# SCH-HC15C_REV1_PG2.net
KiCad netlist of a schematic drawn in Altium Designer
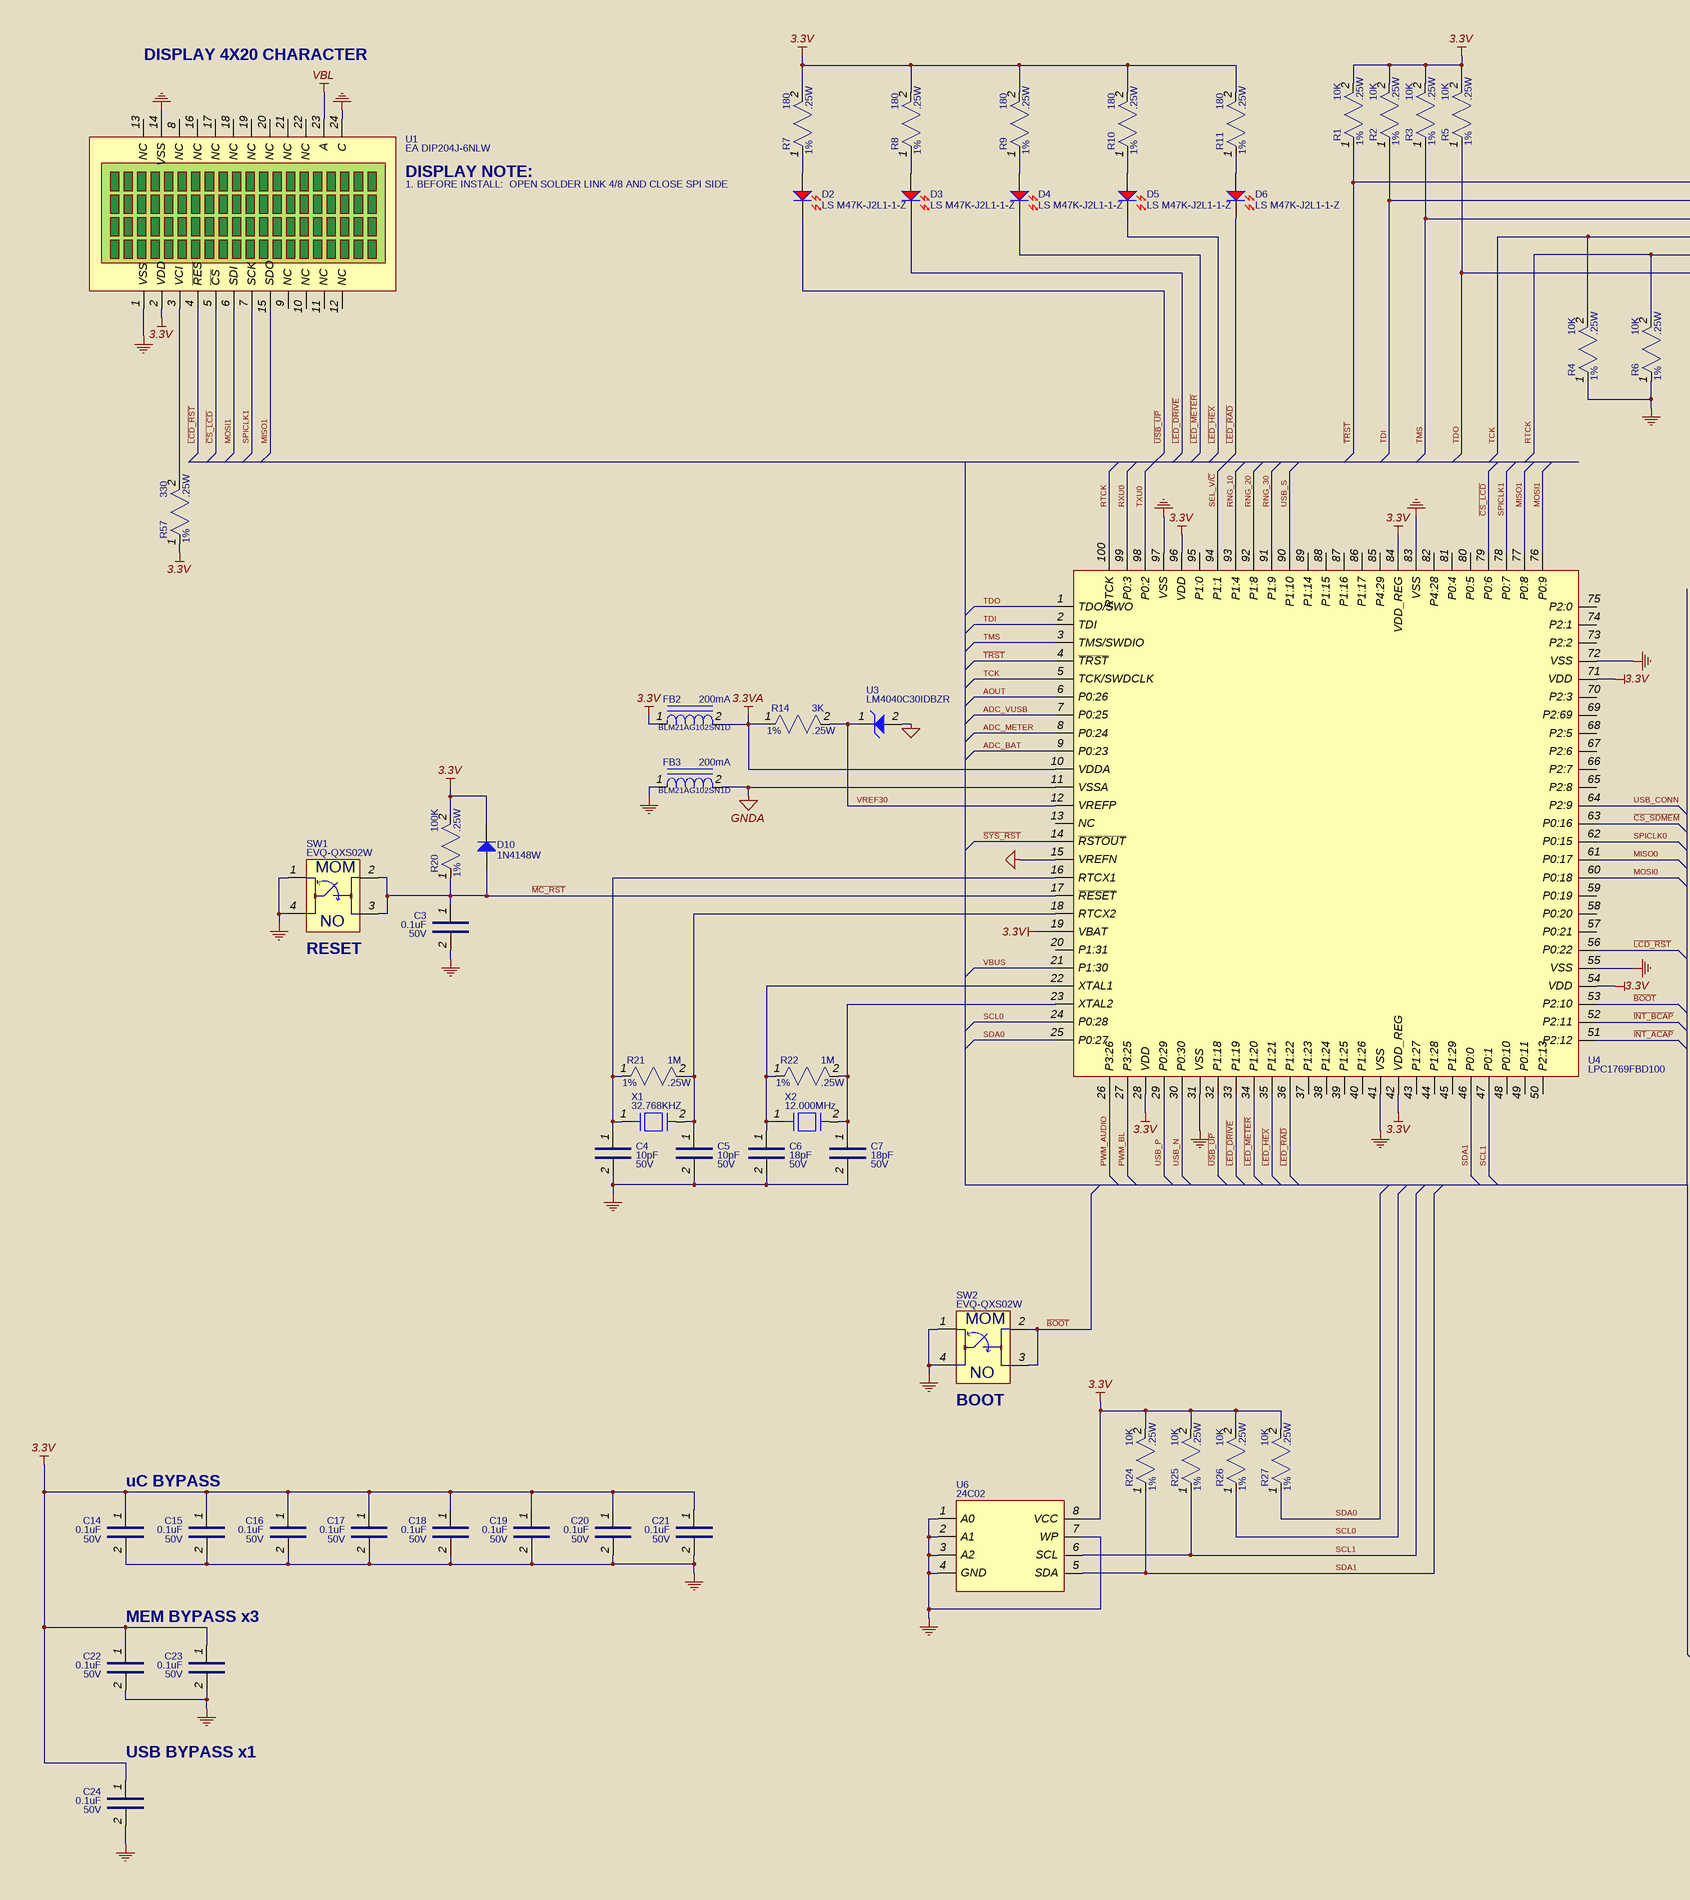
[diagram p0: SCH-HC15C_REV1_PG2.SchDoc, left]
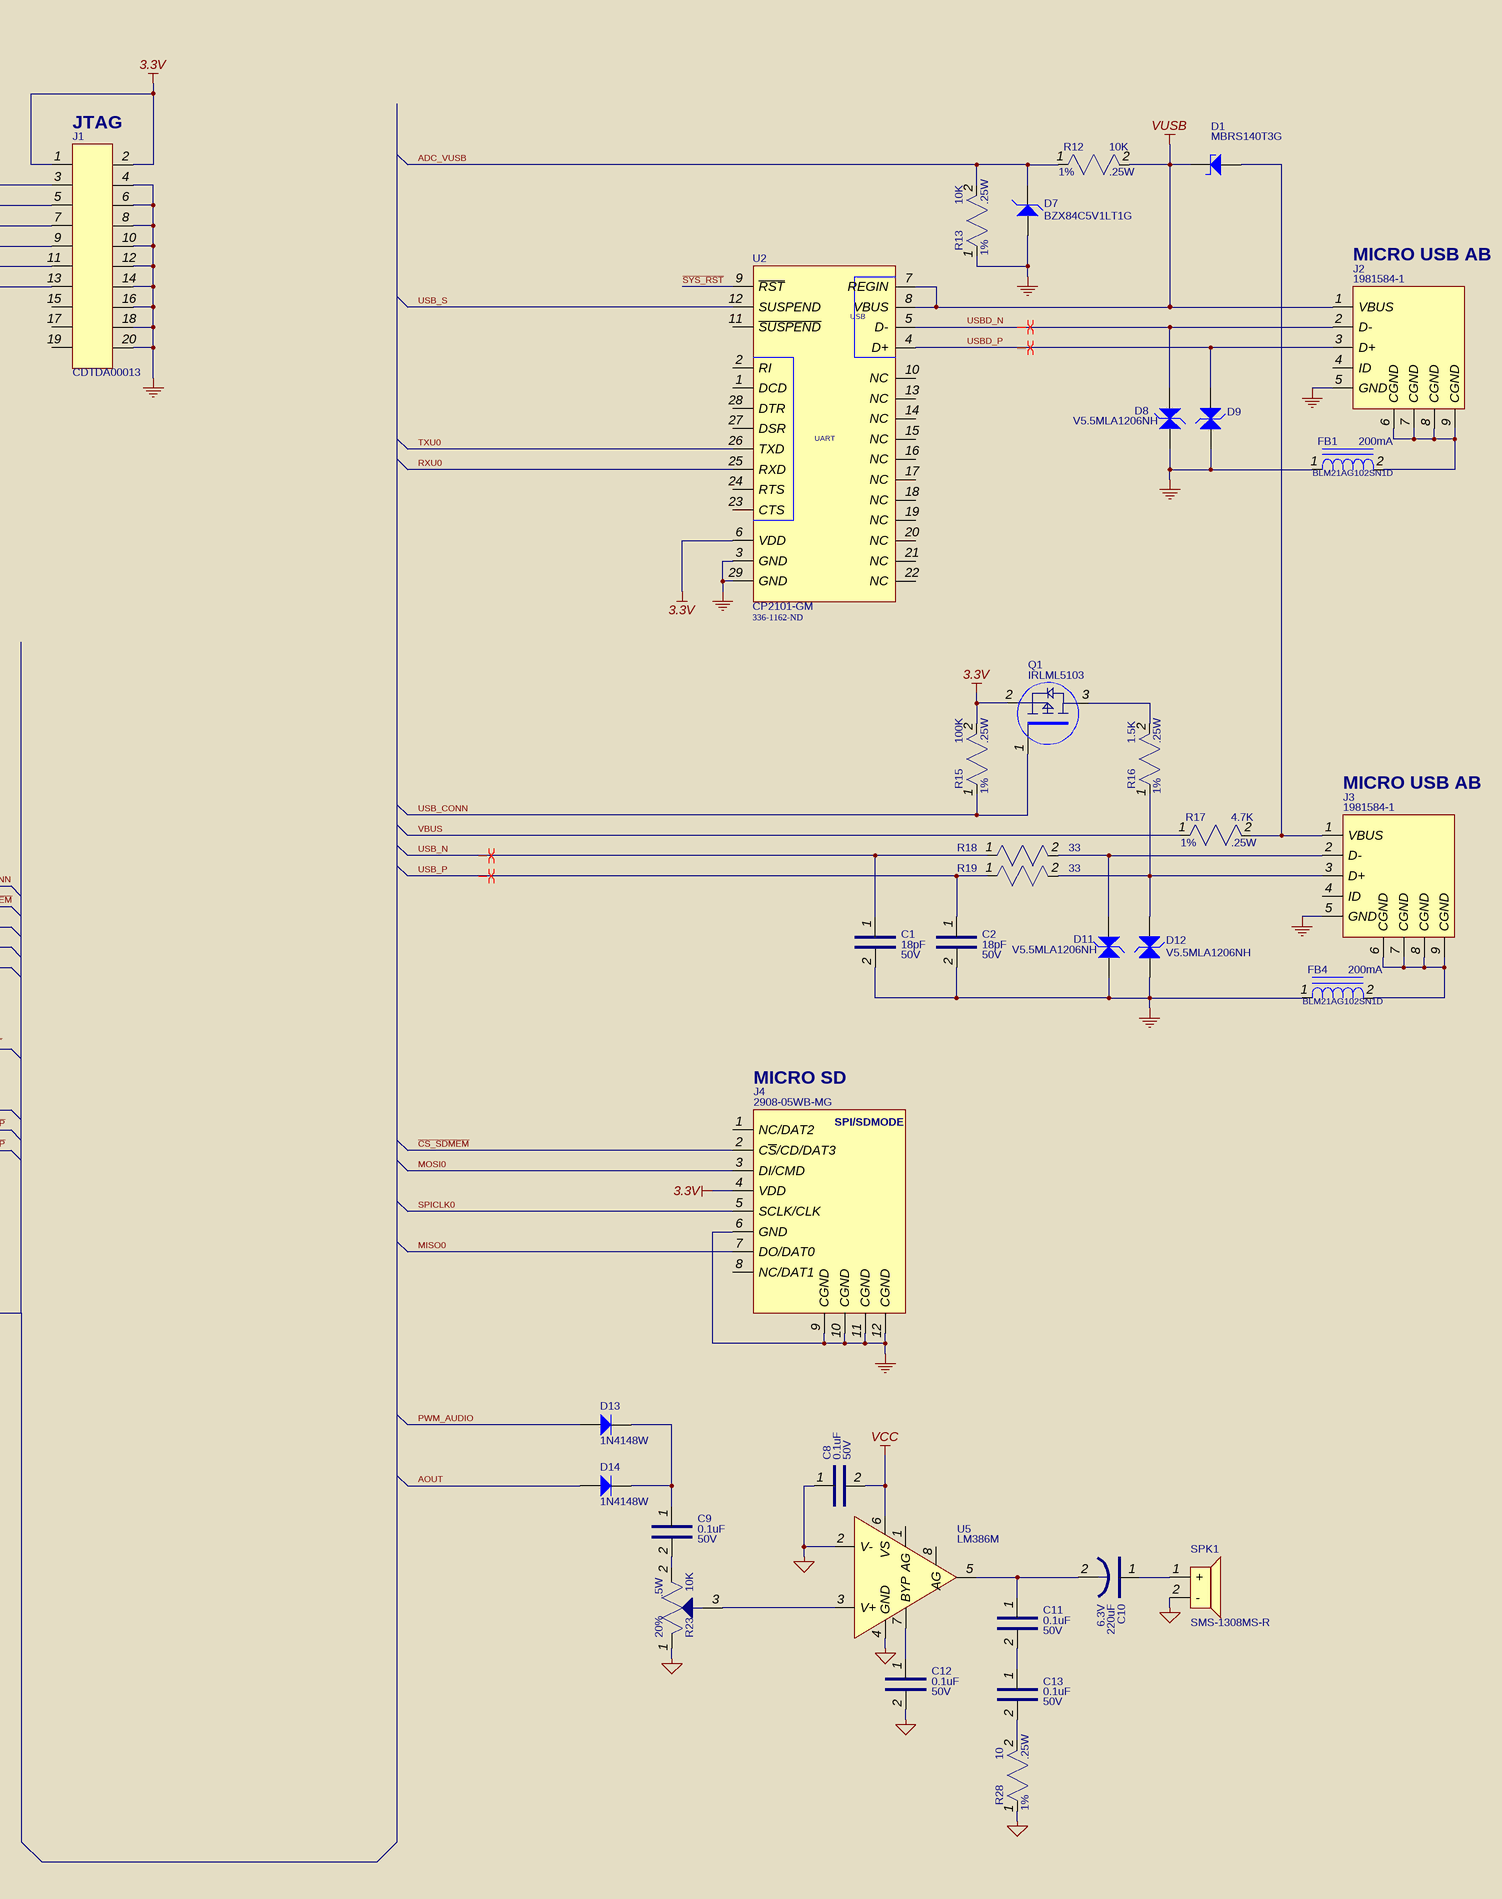
[diagram p1: SCH-HC15C_REV1_PG2.SchDoc, right]

(export (version "E")
  (design (tool "Eeschema 10.0.6"))
  (components
    (comp (ref "C1")
      (value "18pF")
      (footprint "3216[1206] - TAN COLOR")
      (description "CAP, CERAMIC, NPO, 18PF, 50V, 1206, 5%, RoHS")
      (fields (field (name "MFG") "YAGEO") (field (name "TOLERANCE") "10%") (field (name "VOLTAGE") "50V"))
      (libsource (lib "HabLib") (part "CDECA00095"))
    )
    (comp (ref "C2")
      (value "18pF")
      (footprint "3216[1206] - TAN COLOR")
      (description "CAP, CERAMIC, NPO, 18PF, 50V, 1206, 5%, RoHS")
      (fields (field (name "MFG") "YAGEO") (field (name "TOLERANCE") "10%") (field (name "VOLTAGE") "50V"))
      (libsource (lib "HabLib") (part "CDECA00095"))
    )
    (comp (ref "C3")
      (value "0.1uF")
      (footprint "3216[1206] - TAN COLOR")
      (description "CAP, CERAMIC CHIP 0.1UF 10% 50V X7R ROHS")
      (fields (field (name "MFG") "AVX") (field (name "TOLERANCE") "10%") (field (name "VOLTAGE") "50V"))
      (libsource (lib "HabLib") (part "CDECA00070"))
    )
    (comp (ref "C4")
      (value "10pF")
      (footprint "3216[1206] - TAN COLOR")
      (description "CAP, CERAMIC, NPO, 10PF, 50V, 1206, 5%, RoHS")
      (fields (field (name "MFG") "AVX") (field (name "TOLERANCE") "10%") (field (name "VOLTAGE") "50V"))
      (libsource (lib "HabLib") (part "CDECA00143"))
    )
    (comp (ref "C5")
      (value "10pF")
      (footprint "3216[1206] - TAN COLOR")
      (description "CAP, CERAMIC, NPO, 10PF, 50V, 1206, 5%, RoHS")
      (fields (field (name "MFG") "AVX") (field (name "TOLERANCE") "10%") (field (name "VOLTAGE") "50V"))
      (libsource (lib "HabLib") (part "CDECA00143"))
    )
    (comp (ref "C6")
      (value "18pF")
      (footprint "3216[1206] - TAN COLOR")
      (description "CAP, CERAMIC, NPO, 18PF, 50V, 1206, 5%, RoHS")
      (fields (field (name "MFG") "YAGEO") (field (name "TOLERANCE") "10%") (field (name "VOLTAGE") "50V"))
      (libsource (lib "HabLib") (part "CDECA00095"))
    )
    (comp (ref "C7")
      (value "18pF")
      (footprint "3216[1206] - TAN COLOR")
      (description "CAP, CERAMIC, NPO, 18PF, 50V, 1206, 5%, RoHS")
      (fields (field (name "MFG") "YAGEO") (field (name "TOLERANCE") "10%") (field (name "VOLTAGE") "50V"))
      (libsource (lib "HabLib") (part "CDECA00095"))
    )
    (comp (ref "C8")
      (value "0.1uF")
      (footprint "3216[1206] - TAN COLOR")
      (description "CAP, CERAMIC CHIP 0.1UF 10% 50V X7R ROHS")
      (fields (field (name "MFG") "AVX") (field (name "TOLERANCE") "10%") (field (name "VOLTAGE") "50V"))
      (libsource (lib "HabLib") (part "CDECA00070"))
    )
    (comp (ref "C9")
      (value "0.1uF")
      (footprint "3216[1206] - TAN COLOR")
      (description "CAP, CERAMIC CHIP 0.1UF 10% 50V X7R ROHS")
      (fields (field (name "MFG") "AVX") (field (name "TOLERANCE") "10%") (field (name "VOLTAGE") "50V"))
      (libsource (lib "HabLib") (part "CDECA00070"))
    )
    (comp (ref "C10")
      (value "220uF")
      (footprint "CAP_TANT_3528")
      (description "CAP, TANT, 220UF, 6.3V, 20%, LOW ESR, 3528, ROHS")
      (fields (field (name "MFG") "KEMET") (field (name "TOLERANCE") "20%") (field (name "VOLTAGE") "6.3V"))
      (libsource (lib "HabLib") (part "CDECA00139_2"))
    )
    (comp (ref "C11")
      (value "0.1uF")
      (footprint "3216[1206] - TAN COLOR")
      (description "CAP, CERAMIC CHIP 0.1UF 10% 50V X7R ROHS")
      (fields (field (name "MFG") "AVX") (field (name "TOLERANCE") "10%") (field (name "VOLTAGE") "50V"))
      (libsource (lib "HabLib") (part "CDECA00070"))
    )
    (comp (ref "C12")
      (value "0.1uF")
      (footprint "3216[1206] - TAN COLOR")
      (description "CAP, CERAMIC CHIP 0.1UF 10% 50V X7R ROHS")
      (fields (field (name "MFG") "AVX") (field (name "TOLERANCE") "10%") (field (name "VOLTAGE") "50V"))
      (libsource (lib "HabLib") (part "CDECA00070"))
    )
    (comp (ref "C13")
      (value "0.1uF")
      (footprint "3216[1206] - TAN COLOR")
      (description "CAP, CERAMIC CHIP 0.1UF 10% 50V X7R ROHS")
      (fields (field (name "MFG") "AVX") (field (name "TOLERANCE") "10%") (field (name "VOLTAGE") "50V"))
      (libsource (lib "HabLib") (part "CDECA00070"))
    )
    (comp (ref "C14")
      (value "0.1uF")
      (footprint "3216[1206] - TAN COLOR")
      (description "CAP, CERAMIC CHIP 0.1UF 10% 50V X7R ROHS")
      (fields (field (name "MFG") "AVX") (field (name "TOLERANCE") "10%") (field (name "VOLTAGE") "50V"))
      (libsource (lib "HabLib") (part "CDECA00070"))
    )
    (comp (ref "C15")
      (value "0.1uF")
      (footprint "3216[1206] - TAN COLOR")
      (description "CAP, CERAMIC CHIP 0.1UF 10% 50V X7R ROHS")
      (fields (field (name "MFG") "AVX") (field (name "TOLERANCE") "10%") (field (name "VOLTAGE") "50V"))
      (libsource (lib "HabLib") (part "CDECA00070"))
    )
    (comp (ref "C16")
      (value "0.1uF")
      (footprint "3216[1206] - TAN COLOR")
      (description "CAP, CERAMIC CHIP 0.1UF 10% 50V X7R ROHS")
      (fields (field (name "MFG") "AVX") (field (name "TOLERANCE") "10%") (field (name "VOLTAGE") "50V"))
      (libsource (lib "HabLib") (part "CDECA00070"))
    )
    (comp (ref "C17")
      (value "0.1uF")
      (footprint "3216[1206] - TAN COLOR")
      (description "CAP, CERAMIC CHIP 0.1UF 10% 50V X7R ROHS")
      (fields (field (name "MFG") "AVX") (field (name "TOLERANCE") "10%") (field (name "VOLTAGE") "50V"))
      (libsource (lib "HabLib") (part "CDECA00070"))
    )
    (comp (ref "C18")
      (value "0.1uF")
      (footprint "3216[1206] - TAN COLOR")
      (description "CAP, CERAMIC CHIP 0.1UF 10% 50V X7R ROHS")
      (fields (field (name "MFG") "AVX") (field (name "TOLERANCE") "10%") (field (name "VOLTAGE") "50V"))
      (libsource (lib "HabLib") (part "CDECA00070"))
    )
    (comp (ref "C19")
      (value "0.1uF")
      (footprint "3216[1206] - TAN COLOR")
      (description "CAP, CERAMIC CHIP 0.1UF 10% 50V X7R ROHS")
      (fields (field (name "MFG") "AVX") (field (name "TOLERANCE") "10%") (field (name "VOLTAGE") "50V"))
      (libsource (lib "HabLib") (part "CDECA00070"))
    )
    (comp (ref "C20")
      (value "0.1uF")
      (footprint "3216[1206] - TAN COLOR")
      (description "CAP, CERAMIC CHIP 0.1UF 10% 50V X7R ROHS")
      (fields (field (name "MFG") "AVX") (field (name "TOLERANCE") "10%") (field (name "VOLTAGE") "50V"))
      (libsource (lib "HabLib") (part "CDECA00070"))
    )
    (comp (ref "C21")
      (value "0.1uF")
      (footprint "3216[1206] - TAN COLOR")
      (description "CAP, CERAMIC CHIP 0.1UF 10% 50V X7R ROHS")
      (fields (field (name "MFG") "AVX") (field (name "TOLERANCE") "10%") (field (name "VOLTAGE") "50V"))
      (libsource (lib "HabLib") (part "CDECA00070"))
    )
    (comp (ref "C22")
      (value "0.1uF")
      (footprint "3216[1206] - TAN COLOR")
      (description "CAP, CERAMIC CHIP 0.1UF 10% 50V X7R ROHS")
      (fields (field (name "MFG") "AVX") (field (name "TOLERANCE") "10%") (field (name "VOLTAGE") "50V"))
      (libsource (lib "HabLib") (part "CDECA00070"))
    )
    (comp (ref "C23")
      (value "0.1uF")
      (footprint "3216[1206] - TAN COLOR")
      (description "CAP, CERAMIC CHIP 0.1UF 10% 50V X7R ROHS")
      (fields (field (name "MFG") "AVX") (field (name "TOLERANCE") "10%") (field (name "VOLTAGE") "50V"))
      (libsource (lib "HabLib") (part "CDECA00070"))
    )
    (comp (ref "C24")
      (value "0.1uF")
      (footprint "3216[1206] - TAN COLOR")
      (description "CAP, CERAMIC CHIP 0.1UF 10% 50V X7R ROHS")
      (fields (field (name "MFG") "AVX") (field (name "TOLERANCE") "10%") (field (name "VOLTAGE") "50V"))
      (libsource (lib "HabLib") (part "CDECA00070"))
    )
    (comp (ref "D1")
      (value "MBRS140T3G")
      (footprint "DIODE_SMB")
      (description "Diode, Schottky rectifier, 40V, 1A, SMB package, Pb free")
      (fields
        (field (name "MFG") "ON SEMICONDUCTOR")
        (field (name "Comment") "CDEDA00019")
        (field (name "PUBLISHER") "Altium Limited")
      )
      (libsource (lib "HabLib") (part "CDEDA00019"))
    )
    (comp (ref "D2")
      (value "LS M47K-J2L1-1-Z")
      (footprint "OSRAM_XX_M47K")
      (description "DIODE,LED RED UNDER MOUNT SM VF=1.8 I=2MA ROHS")
      (fields (field (name "MFG") "OSRAM") (field (name "Comment") "CDELA00019_1"))
      (libsource (lib "HabLib") (part "CDELA00019_1"))
    )
    (comp (ref "D3")
      (value "LS M47K-J2L1-1-Z")
      (footprint "OSRAM_XX_M47K")
      (description "DIODE,LED RED UNDER MOUNT SM VF=1.8 I=2MA ROHS")
      (fields (field (name "MFG") "OSRAM") (field (name "Comment") "CDELA00019_1"))
      (libsource (lib "HabLib") (part "CDELA00019_1"))
    )
    (comp (ref "D4")
      (value "LS M47K-J2L1-1-Z")
      (footprint "OSRAM_XX_M47K")
      (description "DIODE,LED RED UNDER MOUNT SM VF=1.8 I=2MA ROHS")
      (fields (field (name "MFG") "OSRAM") (field (name "Comment") "CDELA00019_1"))
      (libsource (lib "HabLib") (part "CDELA00019_1"))
    )
    (comp (ref "D5")
      (value "LS M47K-J2L1-1-Z")
      (footprint "OSRAM_XX_M47K")
      (description "DIODE,LED RED UNDER MOUNT SM VF=1.8 I=2MA ROHS")
      (fields (field (name "MFG") "OSRAM") (field (name "Comment") "CDELA00019_1"))
      (libsource (lib "HabLib") (part "CDELA00019_1"))
    )
    (comp (ref "D6")
      (value "LS M47K-J2L1-1-Z")
      (footprint "OSRAM_XX_M47K")
      (description "DIODE,LED RED UNDER MOUNT SM VF=1.8 I=2MA ROHS")
      (fields (field (name "MFG") "OSRAM") (field (name "Comment") "CDELA00019_1"))
      (libsource (lib "HabLib") (part "CDELA00019_1"))
    )
    (comp (ref "D7")
      (value "BZX84C5V1LT1G")
      (footprint "SOT23 - TRANSISTOR")
      (description "DIODE, ZENER, 5.1V, 225MW, SOT-23, ROHS")
      (fields
        (field (name "MFG") "ON SEMICONDUCTOR")
        (field (name "Comment") "CDEDA00043")
        (field (name "PUBLISHER") "Altium Limited")
      )
      (libsource (lib "HabLib") (part "CDEDA00043"))
    )
    (comp (ref "D8")
      (value "V5.5MLA1206NH")
      (footprint "3216[1206]")
      (description "VARISTOR, TVS, 5.5VDC, 1206, 150A, .60J, RoHS")
      (fields (field (name "MFG") "LITTLEFUSE") (field (name "MANUFACTURER") "Littelfuse Inc"))
      (libsource (lib "HabLib") (part "CDEDA00037_1"))
    )
    (comp (ref "D9")
      (value "CDEDA00037_1")
      (footprint "3216[1206]")
      (description "VARISTOR, TVS, 5.5VDC, 1206, 150A, .60J, RoHS")
      (fields (field (name "MFG") "LITTLEFUSE") (field (name "MANUFACTURER") "Littelfuse Inc"))
      (libsource (lib "HabLib") (part "CDEDA00037_1"))
    )
    (comp (ref "D10")
      (value "1N4148W")
      (footprint "HabLib:SOD123")
      (description "DIODE, 150MA, 100V, SOD123")
      (fields
        (field (name "MFG") "DIODES INC")
        (field (name "Comment") "CDEDA00020")
        (field (name "PUBLISHER") "Altium Limited")
      )
      (libsource (lib "HabLib") (part "CDEDA00020"))
    )
    (comp (ref "D11")
      (value "V5.5MLA1206NH")
      (footprint "3216[1206]")
      (description "VARISTOR, TVS, 5.5VDC, 1206, 150A, .60J, RoHS")
      (fields (field (name "MFG") "LITTLEFUSE") (field (name "MANUFACTURER") "Littelfuse Inc"))
      (libsource (lib "HabLib") (part "CDEDA00037_1"))
    )
    (comp (ref "D12")
      (value "V5.5MLA1206NH")
      (footprint "3216[1206]")
      (description "VARISTOR, TVS, 5.5VDC, 1206, 150A, .60J, RoHS")
      (fields (field (name "MFG") "LITTLEFUSE") (field (name "MANUFACTURER") "Littelfuse Inc"))
      (libsource (lib "HabLib") (part "CDEDA00037_1"))
    )
    (comp (ref "D13")
      (value "1N4148W")
      (footprint "SOD123")
      (description "DIODE, 150MA, 100V, SOD123")
      (fields (field (name "MFG") "DIODES INC") (field (name "Comment") "CDEDA00020"))
      (libsource (lib "HabLib") (part "CDEDA00020"))
    )
    (comp (ref "D14")
      (value "1N4148W")
      (footprint "SOD123")
      (description "DIODE, 150MA, 100V, SOD123")
      (fields (field (name "MFG") "DIODES INC") (field (name "Comment") "CDEDA00020"))
      (libsource (lib "HabLib") (part "CDEDA00020"))
    )
    (comp (ref "FB1")
      (value "CDEVA00115")
      (footprint "2012[0805]")
      (description "FERRITE, 1KOHM AT 100MHZ, 220MA, .450DCR")
      (fields
        (field (name "MFG") "MURATA")
        (field (name "TOLERANCE") "10%")
        (field (name "MFG_PN") "BLM21AG102SN1D")
        (field (name "POWER") "200mA")
        (field (name "PUBLISHER") "Altium Limited")
      )
      (libsource (lib "HabLib") (part "CDEVA00115"))
    )
    (comp (ref "FB2")
      (value "CDEVA00115")
      (footprint "2012[0805]")
      (description "FERRITE, 1KOHM AT 100MHZ, 220MA, .450DCR")
      (fields
        (field (name "MFG") "MURATA")
        (field (name "TOLERANCE") "10%")
        (field (name "MFG_PN") "BLM21AG102SN1D")
        (field (name "POWER") "200mA")
        (field (name "PUBLISHER") "Altium Limited")
      )
      (libsource (lib "HabLib") (part "CDEVA00115"))
    )
    (comp (ref "FB3")
      (value "CDEVA00115")
      (footprint "2012[0805]")
      (description "FERRITE, 1KOHM AT 100MHZ, 220MA, .450DCR")
      (fields
        (field (name "MFG") "MURATA")
        (field (name "TOLERANCE") "10%")
        (field (name "MFG_PN") "BLM21AG102SN1D")
        (field (name "POWER") "200mA")
        (field (name "PUBLISHER") "Altium Limited")
      )
      (libsource (lib "HabLib") (part "CDEVA00115"))
    )
    (comp (ref "FB4")
      (value "CDEVA00115")
      (footprint "2012[0805]")
      (description "FERRITE, 1KOHM AT 100MHZ, 220MA, .450DCR")
      (fields
        (field (name "MFG") "MURATA")
        (field (name "TOLERANCE") "10%")
        (field (name "MFG_PN") "BLM21AG102SN1D")
        (field (name "POWER") "200mA")
        (field (name "PUBLISHER") "Altium Limited")
      )
      (libsource (lib "HabLib") (part "CDEVA00115"))
    )
    (comp (ref "J1")
      (value "CDTDA00013")
      (footprint "HDR_2X10_100MIL")
      (description "CONN, HDR, 2X10, 100MIL, TH, ROHS")
      (fields (field (name "MFG") "TYCO ELECTRONICS"))
      (libsource (lib "HabLib") (part "CDTDA00013"))
    )
    (comp (ref "J2")
      (value "1981584-1")
      (footprint "TYCO_1981584-1")
      (description "CONN, RCPTL MICRO USB TYPE AB, SM RA")
      (fields (field (name "MFG") "TYCO") (field (name "Comment") "CDTDA_1"))
      (libsource (lib "HabLib") (part "CDTDA_1"))
    )
    (comp (ref "J3")
      (value "1981584-1")
      (footprint "TYCO_1981584-1")
      (description "CONN, RCPTL MICRO USB TYPE AB, SM RA")
      (fields (field (name "MFG") "TYCO") (field (name "Comment") "CDTDA_1"))
      (libsource (lib "HabLib") (part "CDTDA_1"))
    )
    (comp (ref "J4")
      (value "2908-05WB-MG")
      (footprint "3M_2908-05WB-MG")
      (description "CONN, MICRO SD, SM, ROHS")
      (fields (field (name "MFG") "3M") (field (name "Comment") "CDTDA_2"))
      (libsource (lib "HabLib") (part "CDTDA_2"))
    )
    (comp (ref "Q1")
      (value "IRLML5103")
      (footprint "SOT23 - TRANSISTOR")
      (description "MOSFET P CHN, VDS=30V, RDSON = .6OHM, SOT 23")
      (fields
        (field (name "MFG") "INTERNATIONAL RECTIFIER")
        (field (name "Comment") "CDENA00031")
        (field (name "PUBLISHER") "Altium Limited")
      )
      (libsource (lib "HabLib") (part "CDENA00031"))
    )
    (comp (ref "R1")
      (value "10K")
      (footprint "HabLib:3216[1206]")
      (description "RESISTOR, CHIP 1206 10K OHM 1% 1/4W THICK FILM ROHS")
      (fields
        (field (name "MFG") "PANASONIC")
        (field (name "TOLERANCE") "1%")
        (field (name "POWER") ".25W")
        (field (name "Comment") "CDERA00170")
        (field (name "PUBLISHER") "Altium Limited")
      )
      (libsource (lib "HabLib") (part "CDERA00170"))
    )
    (comp (ref "R2")
      (value "10K")
      (footprint "HabLib:3216[1206]")
      (description "RESISTOR, CHIP 1206 10K OHM 1% 1/4W THICK FILM ROHS")
      (fields
        (field (name "MFG") "PANASONIC")
        (field (name "TOLERANCE") "1%")
        (field (name "POWER") ".25W")
        (field (name "Comment") "CDERA00170")
        (field (name "PUBLISHER") "Altium Limited")
      )
      (libsource (lib "HabLib") (part "CDERA00170"))
    )
    (comp (ref "R3")
      (value "10K")
      (footprint "HabLib:3216[1206]")
      (description "RESISTOR, CHIP 1206 10K OHM 1% 1/4W THICK FILM ROHS")
      (fields
        (field (name "MFG") "PANASONIC")
        (field (name "TOLERANCE") "1%")
        (field (name "POWER") ".25W")
        (field (name "Comment") "CDERA00170")
        (field (name "PUBLISHER") "Altium Limited")
      )
      (libsource (lib "HabLib") (part "CDERA00170"))
    )
    (comp (ref "R4")
      (value "10K")
      (footprint "HabLib:3216[1206]")
      (description "RESISTOR, CHIP 1206 10K OHM 1% 1/4W THICK FILM ROHS")
      (fields
        (field (name "MFG") "PANASONIC")
        (field (name "TOLERANCE") "1%")
        (field (name "POWER") ".25W")
        (field (name "Comment") "CDERA00170")
        (field (name "PUBLISHER") "Altium Limited")
      )
      (libsource (lib "HabLib") (part "CDERA00170"))
    )
    (comp (ref "R5")
      (value "10K")
      (footprint "HabLib:3216[1206]")
      (description "RESISTOR, CHIP 1206 10K OHM 1% 1/4W THICK FILM ROHS")
      (fields
        (field (name "MFG") "PANASONIC")
        (field (name "TOLERANCE") "1%")
        (field (name "POWER") ".25W")
        (field (name "Comment") "CDERA00170")
        (field (name "PUBLISHER") "Altium Limited")
      )
      (libsource (lib "HabLib") (part "CDERA00170"))
    )
    (comp (ref "R6")
      (value "10K")
      (footprint "HabLib:3216[1206]")
      (description "RESISTOR, CHIP 1206 10K OHM 1% 1/4W THICK FILM ROHS")
      (fields
        (field (name "MFG") "PANASONIC")
        (field (name "TOLERANCE") "1%")
        (field (name "POWER") ".25W")
        (field (name "Comment") "CDERA00170")
        (field (name "PUBLISHER") "Altium Limited")
      )
      (libsource (lib "HabLib") (part "CDERA00170"))
    )
    (comp (ref "R7")
      (value "180")
      (footprint "HABLIB:3216[1206]")
      (description "RESISTOR, CHIP 1206 180 OHM 1% 1/4W THICK FILM ROHS")
      (fields
        (field (name "MFG") "PANASONIC")
        (field (name "TOLERANCE") "1%")
        (field (name "POWER") ".25W")
        (field (name "Comment") "CDERA00192")
        (field (name "PUBLISHER") "Altium Limited")
      )
      (libsource (lib "HabLib") (part "CDERA00192"))
    )
    (comp (ref "R8")
      (value "180")
      (footprint "HABLIB:3216[1206]")
      (description "RESISTOR, CHIP 1206 180 OHM 1% 1/4W THICK FILM ROHS")
      (fields
        (field (name "MFG") "PANASONIC")
        (field (name "TOLERANCE") "1%")
        (field (name "POWER") ".25W")
        (field (name "Comment") "CDERA00192")
        (field (name "PUBLISHER") "Altium Limited")
      )
      (libsource (lib "HabLib") (part "CDERA00192"))
    )
    (comp (ref "R9")
      (value "180")
      (footprint "HABLIB:3216[1206]")
      (description "RESISTOR, CHIP 1206 180 OHM 1% 1/4W THICK FILM ROHS")
      (fields
        (field (name "MFG") "PANASONIC")
        (field (name "TOLERANCE") "1%")
        (field (name "POWER") ".25W")
        (field (name "Comment") "CDERA00192")
        (field (name "PUBLISHER") "Altium Limited")
      )
      (libsource (lib "HabLib") (part "CDERA00192"))
    )
    (comp (ref "R10")
      (value "180")
      (footprint "HABLIB:3216[1206]")
      (description "RESISTOR, CHIP 1206 180 OHM 1% 1/4W THICK FILM ROHS")
      (fields
        (field (name "MFG") "PANASONIC")
        (field (name "TOLERANCE") "1%")
        (field (name "POWER") ".25W")
        (field (name "Comment") "CDERA00192")
        (field (name "PUBLISHER") "Altium Limited")
      )
      (libsource (lib "HabLib") (part "CDERA00192"))
    )
    (comp (ref "R11")
      (value "180")
      (footprint "HABLIB:3216[1206]")
      (description "RESISTOR, CHIP 1206 180 OHM 1% 1/4W THICK FILM ROHS")
      (fields
        (field (name "MFG") "PANASONIC")
        (field (name "TOLERANCE") "1%")
        (field (name "POWER") ".25W")
        (field (name "Comment") "CDERA00192")
        (field (name "PUBLISHER") "Altium Limited")
      )
      (libsource (lib "HabLib") (part "CDERA00192"))
    )
    (comp (ref "R12")
      (value "10K")
      (footprint "HabLib:3216[1206]")
      (description "RESISTOR, CHIP 1206 10K OHM 1% 1/4W THICK FILM ROHS")
      (fields
        (field (name "MFG") "PANASONIC")
        (field (name "TOLERANCE") "1%")
        (field (name "POWER") ".25W")
        (field (name "Comment") "CDERA00170")
        (field (name "PUBLISHER") "Altium Limited")
      )
      (libsource (lib "HabLib") (part "CDERA00170"))
    )
    (comp (ref "R13")
      (value "10K")
      (footprint "HabLib:3216[1206]")
      (description "RESISTOR, CHIP 1206 10K OHM 1% 1/4W THICK FILM ROHS")
      (fields
        (field (name "MFG") "PANASONIC")
        (field (name "TOLERANCE") "1%")
        (field (name "POWER") ".25W")
        (field (name "Comment") "CDERA00170")
        (field (name "PUBLISHER") "Altium Limited")
      )
      (libsource (lib "HabLib") (part "CDERA00170"))
    )
    (comp (ref "R14")
      (value "3K")
      (footprint "HABLIB:3216[1206]")
      (description "RESISTOR, CHIP 1206 3K OHM 1% 1/4W THICK FILM ROHS")
      (fields
        (field (name "MFG") "PANASONIC")
        (field (name "TOLERANCE") "1%")
        (field (name "POWER") ".25W")
        (field (name "Comment") "CDERA00275_9")
        (field (name "PUBLISHER") "Altium Limited")
      )
      (libsource (lib "HabLib") (part "CDERA00275_9"))
    )
    (comp (ref "R15")
      (value "100K")
      (footprint "HABLIB:3216[1206]")
      (description "RESISTOR, CHIP 1206 100K OHM 1% 1/4W THICK FILM ROHS")
      (fields
        (field (name "MFG") "PANASONIC")
        (field (name "TOLERANCE") "1%")
        (field (name "POWER") ".25W")
        (field (name "Comment") "CDERA00198")
        (field (name "PUBLISHER") "Altium Limited")
      )
      (libsource (lib "HabLib") (part "CDERA00198"))
    )
    (comp (ref "R16")
      (value "1.5K")
      (footprint "HabLib:3216[1206]")
      (description "RESISTOR, CHIP 1206 1.5K OHM 1% 1/4W THICK FILM ROHS")
      (fields
        (field (name "MFG") "PANASONIC")
        (field (name "TOLERANCE") "1%")
        (field (name "POWER") ".25W")
        (field (name "Comment") "CDERA00179")
        (field (name "PUBLISHER") "Altium Limited")
      )
      (libsource (lib "HabLib") (part "CDERA00179"))
    )
    (comp (ref "R17")
      (value "4.7K")
      (footprint "HABLIB:3216[1206]")
      (description "RESISTOR, CHIP 1206 4.7K OHM 1% 1/4W THICK FILM ROHS")
      (fields
        (field (name "MFG") "PANASONIC")
        (field (name "TOLERANCE") "1%")
        (field (name "POWER") ".25W")
        (field (name "Comment") "CDERA00169")
        (field (name "PUBLISHER") "Altium Limited")
      )
      (libsource (lib "HabLib") (part "CDERA00169"))
    )
    (comp (ref "R18")
      (value "33")
      (footprint "HABLIB:3216[1206]")
      (description "RESISTOR, CHIP 1206 33 OHM 1% 1/4W THICK FILM ROHS")
      (fields (field (name "MFG") "PANASONIC") (field (name "TOLERANCE") "1%"))
      (libsource (lib "HabLib") (part "CDERA00207"))
    )
    (comp (ref "R19")
      (value "33")
      (footprint "HABLIB:3216[1206]")
      (description "RESISTOR, CHIP 1206 33 OHM 1% 1/4W THICK FILM ROHS")
      (fields (field (name "MFG") "PANASONIC") (field (name "TOLERANCE") "1%"))
      (libsource (lib "HabLib") (part "CDERA00207"))
    )
    (comp (ref "R20")
      (value "100K")
      (footprint "HABLIB:3216[1206]")
      (description "RESISTOR, CHIP 1206 100K OHM 1% 1/4W THICK FILM ROHS")
      (fields
        (field (name "MFG") "PANASONIC")
        (field (name "TOLERANCE") "1%")
        (field (name "POWER") ".25W")
        (field (name "Comment") "CDERA00198")
        (field (name "PUBLISHER") "Altium Limited")
      )
      (libsource (lib "HabLib") (part "CDERA00198"))
    )
    (comp (ref "R21")
      (value "1M")
      (footprint "HABLIB:3216[1206]")
      (description "RESISTOR, CHIP 1206 1MOHM 1% 1/4W THICK FILM ROHS")
      (fields
        (field (name "MFG") "PANASONIC")
        (field (name "TOLERANCE") "1%")
        (field (name "POWER") ".25W")
        (field (name "Comment") "CDERA00191")
        (field (name "PUBLISHER") "Altium Limited")
      )
      (libsource (lib "HabLib") (part "CDERA00191"))
    )
    (comp (ref "R22")
      (value "1M")
      (footprint "HABLIB:3216[1206]")
      (description "RESISTOR, CHIP 1206 1MOHM 1% 1/4W THICK FILM ROHS")
      (fields
        (field (name "MFG") "PANASONIC")
        (field (name "TOLERANCE") "1%")
        (field (name "POWER") ".25W")
        (field (name "Comment") "CDERA00191")
        (field (name "PUBLISHER") "Altium Limited")
      )
      (libsource (lib "HabLib") (part "CDERA00191"))
    )
    (comp (ref "R23")
      (value "10K")
      (footprint "BOURNS_3352")
      (description "RESISTOR, POT 10K OHM 20% THUMBWHELL, CERM, TH, ROHS")
      (fields
        (field (name "MFG") "BOURNS")
        (field (name "TOLERANCE") "20%")
        (field (name "POWER") ".5W")
        (field (name "Comment") "CDERA00207_2")
      )
      (libsource (lib "HabLib") (part "CDERA00207_2"))
    )
    (comp (ref "R24")
      (value "10K")
      (footprint "HabLib:3216[1206]")
      (description "RESISTOR, CHIP 1206 10K OHM 1% 1/4W THICK FILM ROHS")
      (fields
        (field (name "MFG") "PANASONIC")
        (field (name "TOLERANCE") "1%")
        (field (name "POWER") ".25W")
        (field (name "Comment") "CDERA00170")
        (field (name "PUBLISHER") "Altium Limited")
      )
      (libsource (lib "HabLib") (part "CDERA00170"))
    )
    (comp (ref "R25")
      (value "10K")
      (footprint "HabLib:3216[1206]")
      (description "RESISTOR, CHIP 1206 10K OHM 1% 1/4W THICK FILM ROHS")
      (fields
        (field (name "MFG") "PANASONIC")
        (field (name "TOLERANCE") "1%")
        (field (name "POWER") ".25W")
        (field (name "Comment") "CDERA00170")
        (field (name "PUBLISHER") "Altium Limited")
      )
      (libsource (lib "HabLib") (part "CDERA00170"))
    )
    (comp (ref "R26")
      (value "10K")
      (footprint "HabLib:3216[1206]")
      (description "RESISTOR, CHIP 1206 10K OHM 1% 1/4W THICK FILM ROHS")
      (fields
        (field (name "MFG") "PANASONIC")
        (field (name "TOLERANCE") "1%")
        (field (name "POWER") ".25W")
        (field (name "Comment") "CDERA00170")
        (field (name "PUBLISHER") "Altium Limited")
      )
      (libsource (lib "HabLib") (part "CDERA00170"))
    )
    (comp (ref "R27")
      (value "10K")
      (footprint "HabLib:3216[1206]")
      (description "RESISTOR, CHIP 1206 10K OHM 1% 1/4W THICK FILM ROHS")
      (fields
        (field (name "MFG") "PANASONIC")
        (field (name "TOLERANCE") "1%")
        (field (name "POWER") ".25W")
        (field (name "Comment") "CDERA00170")
        (field (name "PUBLISHER") "Altium Limited")
      )
      (libsource (lib "HabLib") (part "CDERA00170"))
    )
    (comp (ref "R28")
      (value "10")
      (footprint "HABLIB:3216[1206]")
      (description "RESISTOR, CHIP 1206 10 OHM 1% 1/4W THICK FILM ROHS")
      (fields
        (field (name "MFG") "PANASONIC")
        (field (name "TOLERANCE") "1%")
        (field (name "POWER") ".25W")
        (field (name "Comment") "CDERA00142")
      )
      (libsource (lib "HabLib") (part "CDERA00142"))
    )
    (comp (ref "R57")
      (value "330")
      (footprint "HABLIB:3216[1206]")
      (description "RESISTOR, CHIP 1206 330 OHM 1% 1/4W THICK FILM ROHS")
      (fields
        (field (name "MFG") "PANASONIC")
        (field (name "TOLERANCE") "1%")
        (field (name "POWER") ".25W")
        (field (name "Comment") "CDERA00154")
        (field (name "PUBLISHER") "Altium Limited")
      )
      (libsource (lib "HabLib") (part "CDERA00154"))
    )
    (comp (ref "SPK1")
      (value "CDEVA_2")
      (footprint "PUI_AUDIO_SMS-1308MS-R")
      (description "SPEAKER 8OHM .7W 88DB 13MM SMD")
      (fields (field (name "MFG") "PUI AUDIO") (field (name "MFG_PN") "SMS-1308MS-R"))
      (libsource (lib "HabLib") (part "CDEVA_2"))
    )
    (comp (ref "SW1")
      (value "EVQ-QXS02W")
      (footprint "PANASONIC_EVQQX")
      (description "SWITCH, MOM, NO, SM")
      (fields
        (field (name "MFG") "PANASONIC")
        (field (name "Comment") "CDESA00095")
        (field (name "PUBLISHER") "Altium Limited")
      )
      (libsource (lib "HabLib") (part "CDESA00095"))
    )
    (comp (ref "SW2")
      (value "EVQ-QXS02W")
      (footprint "PANASONIC_EVQQX")
      (description "SWITCH, MOM, NO, SM")
      (fields
        (field (name "MFG") "PANASONIC")
        (field (name "Comment") "CDESA00095")
        (field (name "PUBLISHER") "Altium Limited")
      )
      (libsource (lib "HabLib") (part "CDESA00095"))
    )
    (comp (ref "U1")
      (value "EA DIP204J-6NLW")
      (footprint "EA_790-EADIP204J6NLW")
      (description "LCD, 4X20 WITH ICONS, SERIAL INTERFACE, 5X8DOT, WHITE BACKLIGHT")
      (fields (field (name "MFG") "ELECTRONIC ASSEMBLY") (field (name "Comment") "CDELA00023_1"))
      (libsource (lib "HabLib") (part "CDELA00023_1"))
    )
    (comp (ref "U2")
      (value "CP2101-GM")
      (footprint "QFN50P500X500-28VBM-MODIFIED")
      (description "IC, TXRX USB TO UART BRIDGE, ROHS, 28QFN")
      (fields
        (field (name "MFG") "SILICON LABS")
        (field (name "SUPPLIER PART NUMBER 1") "336-1162-ND")
        (field (name "Comment") "CDEUA00070_1")
      )
      (libsource (lib "HabLib") (part "CDEUA00070_1"))
    )
    (comp (ref "U3")
      (value "LM4040C30IDBZR")
      (footprint "SOT23 - TRANSISTOR")
      (description "IC, SHUNT VOLTAGE REFERENCE")
      (fields (field (name "MFG") "TEXAS INSTRUMENTS") (field (name "Comment") "CDEUA00049"))
      (libsource (lib "HabLib") (part "CDEUA00049"))
    )
    (comp (ref "U4")
      (value "CDEUA00069_2")
      (footprint "SQFP50P1600X1600-100M_MODIFIED")
      (description "IC, MICRO CONTROLLER, 512KB FLASH, 64K, ARM CORTEX M3, 100LQFP")
      (fields (field (name "MFG") "NXP") (field (name "MFG_PN") "LPC1769FBD100"))
      (libsource (lib "HabLib") (part "CDEUA00069_2"))
    )
    (comp (ref "U5")
      (value "LM386M")
      (footprint "MUA08A")
      (description "IC AUDIO AMP, CLASS AB, 325mW, 8SOIC, ROHS")
      (fields (field (name "MFG") "NATIONAL SEMICONDUCTOR") (field (name "Comment") "CDEUA00071_1"))
      (libsource (lib "HabLib") (part "CDEUA00071_1"))
    )
    (comp (ref "U6")
      (value "24C02")
      (footprint "S8_N: Linear Tech SO8 NARROW")
      (description "IC, EEPROM, I2C, 256x8, 8PIN SO8, ROHOS")
      (fields
        (field (name "MFG") "ATMEL")
        (field (name "Comment") "CDEUA00020")
        (field (name "PUBLISHER") "Altium Limited")
      )
      (libsource (lib "HabLib") (part "CDEUA00020"))
    )
    (comp (ref "X1")
      (value "32.768KHZ")
      (footprint "CITIZEN_CMR200T")
      (description "CRYSTAL, 32.768KHZ, 12.5PF, SMT SM CYLINDRICAL CAN")
      (fields (field (name "MFG") "CITIZEN") (field (name "TOLERANCE") "20ppm"))
      (libsource (lib "HabLib") (part "CDEKA00015"))
    )
    (comp (ref "X2")
      (value "12.000MHz")
      (footprint "HC49/US-SM")
      (description "CRYSTAL, 12.000MHZ, 18PF, SMT HC49/US")
      (fields (field (name "MFG") "CITIZEN") (field (name "TOLERANCE") "30ppm"))
      (libsource (lib "HabLib") (part "CDEKA00019"))
    )
  )
  (nets
    (net (code "1") (name "/ADC_BAT") (class "Default")
      (node (ref "U4") (pin "9") (pinfunction "P0:23_9") (pintype "passive"))
    )
    (net (code "2") (name "/ADC_METER") (class "Default")
      (node (ref "U4") (pin "8") (pinfunction "P0:24_8") (pintype "passive"))
    )
    (net (code "3") (name "/ADC_VUSB") (class "Default")
      (node (ref "D7") (pin "3") (pinfunction "K_3") (pintype "passive"))
      (node (ref "R12") (pin "1") (pinfunction "1_1") (pintype "passive"))
      (node (ref "R13") (pin "2") (pinfunction "2_2") (pintype "passive"))
      (node (ref "U4") (pin "7") (pinfunction "P0:25_7") (pintype "passive"))
    )
    (net (code "4") (name "/AOUT") (class "Default")
      (node (ref "D14") (pin "1") (pinfunction "A_1") (pintype "passive"))
      (node (ref "U4") (pin "6") (pinfunction "P0:26_6") (pintype "passive"))
    )
    (net (code "5") (name "/BOOT") (class "Default")
      (node (ref "SW2") (pin "2") (pintype "passive"))
      (node (ref "SW2") (pin "3") (pintype "passive"))
      (node (ref "U4") (pin "53") (pinfunction "P2:10_53") (pintype "passive"))
    )
    (net (code "6") (name "/CS_LCD") (class "Default")
      (node (ref "U1") (pin "5") (pinfunction "CS_5") (pintype "passive"))
      (node (ref "U4") (pin "79") (pinfunction "P0:6_79") (pintype "passive"))
    )
    (net (code "7") (name "/CS_SDMEM") (class "Default")
      (node (ref "J4") (pin "2") (pinfunction "C~{S}/CD/DAT3_2") (pintype "passive"))
      (node (ref "U4") (pin "63") (pinfunction "P0:16_63") (pintype "passive"))
    )
    (net (code "8") (name "/INT_ACAP") (class "Default")
      (node (ref "U4") (pin "51") (pinfunction "P2:12_51") (pintype "passive"))
    )
    (net (code "9") (name "/INT_BCAP") (class "Default")
      (node (ref "U4") (pin "52") (pinfunction "P2:11_52") (pintype "passive"))
    )
    (net (code "10") (name "/LCD_RST") (class "Default")
      (node (ref "U1") (pin "4") (pinfunction "RES_4") (pintype "passive"))
      (node (ref "U4") (pin "56") (pinfunction "P0:22_56") (pintype "passive"))
    )
    (net (code "11") (name "/LED_DRIVE") (class "Default")
      (node (ref "D3") (pin "2") (pinfunction "K_2") (pintype "passive"))
      (node (ref "U4") (pin "33") (pinfunction "P1:19_33") (pintype "passive"))
    )
    (net (code "12") (name "/LED_HEX") (class "Default")
      (node (ref "D5") (pin "2") (pinfunction "K_2") (pintype "passive"))
      (node (ref "U4") (pin "35") (pinfunction "P1:21_35") (pintype "passive"))
    )
    (net (code "13") (name "/LED_METER") (class "Default")
      (node (ref "D4") (pin "2") (pinfunction "K_2") (pintype "passive"))
      (node (ref "U4") (pin "34") (pinfunction "P1:20_34") (pintype "passive"))
    )
    (net (code "14") (name "/LED_RAD") (class "Default")
      (node (ref "D6") (pin "2") (pinfunction "K_2") (pintype "passive"))
      (node (ref "U4") (pin "36") (pinfunction "P1:22_36") (pintype "passive"))
    )
    (net (code "15") (name "/MC_RST") (class "Default")
      (node (ref "C3") (pin "1") (pinfunction "1_1") (pintype "passive"))
      (node (ref "D10") (pin "1") (pinfunction "A_1") (pintype "passive"))
      (node (ref "R20") (pin "1") (pinfunction "1_1") (pintype "passive"))
      (node (ref "SW1") (pin "2") (pintype "passive"))
      (node (ref "SW1") (pin "3") (pintype "passive"))
      (node (ref "U4") (pin "17") (pinfunction "RESET_17") (pintype "passive"))
    )
    (net (code "16") (name "/MISO0") (class "Default")
      (node (ref "J4") (pin "7") (pinfunction "DO/DAT0_7") (pintype "passive"))
      (node (ref "U4") (pin "61") (pinfunction "P0:17_61") (pintype "passive"))
    )
    (net (code "17") (name "/MISO1") (class "Default")
      (node (ref "U1") (pin "15") (pinfunction "SDO_15") (pintype "passive"))
      (node (ref "U4") (pin "77") (pinfunction "P0:8_77") (pintype "passive"))
    )
    (net (code "18") (name "/MOSI0") (class "Default")
      (node (ref "J4") (pin "3") (pinfunction "DI/CMD_3") (pintype "passive"))
      (node (ref "U4") (pin "60") (pinfunction "P0:18_60") (pintype "passive"))
    )
    (net (code "19") (name "/MOSI1") (class "Default")
      (node (ref "U1") (pin "6") (pinfunction "SDI_6") (pintype "passive"))
      (node (ref "U4") (pin "76") (pinfunction "P0:9_76") (pintype "passive"))
    )
    (net (code "20") (name "/PWM_AUDIO") (class "Default")
      (node (ref "D13") (pin "1") (pinfunction "A_1") (pintype "passive"))
      (node (ref "U4") (pin "26") (pinfunction "P3:26_26") (pintype "passive"))
    )
    (net (code "21") (name "/PWM_BL") (class "Default")
      (node (ref "U4") (pin "27") (pinfunction "P3:25_27") (pintype "passive"))
    )
    (net (code "22") (name "/RNG_10") (class "Default")
      (node (ref "U4") (pin "93") (pinfunction "P1:4_93") (pintype "passive"))
    )
    (net (code "23") (name "/RNG_20") (class "Default")
      (node (ref "U4") (pin "92") (pinfunction "P1:8_92") (pintype "passive"))
    )
    (net (code "24") (name "/RNG_30") (class "Default")
      (node (ref "U4") (pin "91") (pinfunction "P1:9_91") (pintype "passive"))
    )
    (net (code "25") (name "/RTCK") (class "Default")
      (node (ref "J1") (pin "11") (pinfunction "11_11") (pintype "passive"))
      (node (ref "R6") (pin "2") (pinfunction "2_2") (pintype "passive"))
      (node (ref "U4") (pin "100") (pinfunction "RTCK_100") (pintype "passive"))
    )
    (net (code "26") (name "/RXU0") (class "Default")
      (node (ref "U2") (pin "25") (pinfunction "RXD_25") (pintype "passive"))
      (node (ref "U4") (pin "99") (pinfunction "P0:3_99") (pintype "passive"))
    )
    (net (code "27") (name "/SCL0") (class "Default")
      (node (ref "R26") (pin "1") (pinfunction "1_1") (pintype "passive"))
      (node (ref "U4") (pin "24") (pinfunction "P0:28_24") (pintype "passive"))
    )
    (net (code "28") (name "/SCL1") (class "Default")
      (node (ref "R25") (pin "1") (pinfunction "1_1") (pintype "passive"))
      (node (ref "U4") (pin "47") (pinfunction "P0:1_47") (pintype "passive"))
      (node (ref "U6") (pin "6") (pinfunction "SCL_6") (pintype "passive"))
    )
    (net (code "29") (name "/SDA0") (class "Default")
      (node (ref "R27") (pin "1") (pinfunction "1_1") (pintype "passive"))
      (node (ref "U4") (pin "25") (pinfunction "P0:27_25") (pintype "passive"))
    )
    (net (code "30") (name "/SDA1") (class "Default")
      (node (ref "R24") (pin "1") (pinfunction "1_1") (pintype "passive"))
      (node (ref "U4") (pin "46") (pinfunction "P0:0_46") (pintype "passive"))
      (node (ref "U6") (pin "5") (pinfunction "SDA_5") (pintype "passive"))
    )
    (net (code "31") (name "/SEL_V{slash}~{C}") (class "Default")
      (node (ref "U4") (pin "94") (pinfunction "P1:1_94") (pintype "passive"))
    )
    (net (code "32") (name "/SPICLK0") (class "Default")
      (node (ref "J4") (pin "5") (pinfunction "SCLK/CLK_5") (pintype "passive"))
      (node (ref "U4") (pin "62") (pinfunction "P0:15_62") (pintype "passive"))
    )
    (net (code "33") (name "/SPICLK1") (class "Default")
      (node (ref "U1") (pin "7") (pinfunction "SCK_7") (pintype "passive"))
      (node (ref "U4") (pin "78") (pinfunction "P0:7_78") (pintype "passive"))
    )
    (net (code "34") (name "/SYS_RST") (class "Default")
      (node (ref "U2") (pin "9") (pinfunction "RST_9") (pintype "passive"))
      (node (ref "U4") (pin "14") (pinfunction "RSTOUT_14") (pintype "passive"))
    )
    (net (code "35") (name "/TCK") (class "Default")
      (node (ref "J1") (pin "9") (pinfunction "9_9") (pintype "passive"))
      (node (ref "R4") (pin "2") (pinfunction "2_2") (pintype "passive"))
      (node (ref "U4") (pin "5") (pinfunction "TCK/SWDCLK_5") (pintype "passive"))
    )
    (net (code "36") (name "/TDI") (class "Default")
      (node (ref "J1") (pin "5") (pinfunction "5_5") (pintype "passive"))
      (node (ref "R2") (pin "1") (pinfunction "1_1") (pintype "passive"))
      (node (ref "U4") (pin "2") (pinfunction "TDI_2") (pintype "passive"))
    )
    (net (code "37") (name "/TDO") (class "Default")
      (node (ref "J1") (pin "13") (pinfunction "13_13") (pintype "passive"))
      (node (ref "R5") (pin "1") (pinfunction "1_1") (pintype "passive"))
      (node (ref "U4") (pin "1") (pinfunction "TDO/SWO_1") (pintype "passive"))
    )
    (net (code "38") (name "/TMS") (class "Default")
      (node (ref "J1") (pin "7") (pinfunction "7_7") (pintype "passive"))
      (node (ref "R3") (pin "1") (pinfunction "1_1") (pintype "passive"))
      (node (ref "U4") (pin "3") (pinfunction "TMS/SWDIO_3") (pintype "passive"))
    )
    (net (code "39") (name "/TRST") (class "Default")
      (node (ref "J1") (pin "3") (pinfunction "3_3") (pintype "passive"))
      (node (ref "R1") (pin "1") (pinfunction "1_1") (pintype "passive"))
      (node (ref "U4") (pin "4") (pinfunction "TRST_4") (pintype "passive"))
    )
    (net (code "40") (name "/TXU0") (class "Default")
      (node (ref "U2") (pin "26") (pinfunction "TXD_26") (pintype "passive"))
      (node (ref "U4") (pin "98") (pinfunction "P0:2_98") (pintype "passive"))
    )
    (net (code "41") (name "/USBD_N") (class "Default")
      (node (ref "D8") (pin "2") (pinfunction "K_2") (pintype "passive"))
      (node (ref "J2") (pin "2") (pinfunction "D-_2") (pintype "passive"))
      (node (ref "U2") (pin "5") (pinfunction "D-_5") (pintype "passive"))
    )
    (net (code "42") (name "/USBD_P") (class "Default")
      (node (ref "D9") (pin "2") (pinfunction "K_2") (pintype "passive"))
      (node (ref "J2") (pin "3") (pinfunction "D+_3") (pintype "passive"))
      (node (ref "U2") (pin "4") (pinfunction "D+_4") (pintype "passive"))
    )
    (net (code "43") (name "/USB_CONN") (class "Default")
      (node (ref "Q1") (pin "1") (pinfunction "B_1") (pintype "passive"))
      (node (ref "R15") (pin "1") (pinfunction "1_1") (pintype "passive"))
      (node (ref "U4") (pin "64") (pinfunction "P2:9_64") (pintype "passive"))
    )
    (net (code "44") (name "/USB_N") (class "Default")
      (node (ref "C1") (pin "1") (pinfunction "1_1") (pintype "passive"))
      (node (ref "R18") (pin "1") (pinfunction "1_1") (pintype "passive"))
      (node (ref "U4") (pin "30") (pinfunction "P0:30_30") (pintype "passive"))
    )
    (net (code "45") (name "/USB_P") (class "Default")
      (node (ref "C2") (pin "1") (pinfunction "1_1") (pintype "passive"))
      (node (ref "R19") (pin "1") (pinfunction "1_1") (pintype "passive"))
      (node (ref "U4") (pin "29") (pinfunction "P0:29_29") (pintype "passive"))
    )
    (net (code "46") (name "/USB_S") (class "Default")
      (node (ref "U2") (pin "12") (pinfunction "SUSPEND_12") (pintype "passive"))
      (node (ref "U4") (pin "90") (pinfunction "P1:10_90") (pintype "passive"))
    )
    (net (code "47") (name "/USB_UP") (class "Default")
      (node (ref "D2") (pin "2") (pinfunction "K_2") (pintype "passive"))
      (node (ref "U4") (pin "32") (pinfunction "P1:18_32") (pintype "passive"))
    )
    (net (code "48") (name "/VBUS") (class "Default")
      (node (ref "R17") (pin "1") (pinfunction "1_1") (pintype "passive"))
      (node (ref "U4") (pin "21") (pinfunction "P1:30_21") (pintype "passive"))
    )
    (net (code "49") (name "/VREF30") (class "Default")
      (node (ref "R14") (pin "2") (pinfunction "2_2") (pintype "passive"))
      (node (ref "U3") (pin "1") (pinfunction "K_1") (pintype "passive"))
      (node (ref "U4") (pin "12") (pinfunction "VREFP_12") (pintype "passive"))
    )
    (net (code "50") (name "3.3V") (class "Default")
      (node (ref "C14") (pin "1") (pinfunction "1_1") (pintype "passive"))
      (node (ref "C15") (pin "1") (pinfunction "1_1") (pintype "passive"))
      (node (ref "C16") (pin "1") (pinfunction "1_1") (pintype "passive"))
      (node (ref "C17") (pin "1") (pinfunction "1_1") (pintype "passive"))
      (node (ref "C18") (pin "1") (pinfunction "1_1") (pintype "passive"))
      (node (ref "C19") (pin "1") (pinfunction "1_1") (pintype "passive"))
      (node (ref "C20") (pin "1") (pinfunction "1_1") (pintype "passive"))
      (node (ref "C21") (pin "1") (pinfunction "1_1") (pintype "passive"))
      (node (ref "C22") (pin "1") (pinfunction "1_1") (pintype "passive"))
      (node (ref "C23") (pin "1") (pinfunction "1_1") (pintype "passive"))
      (node (ref "C24") (pin "1") (pinfunction "1_1") (pintype "passive"))
      (node (ref "D10") (pin "2") (pinfunction "K_2") (pintype "passive"))
      (node (ref "FB2") (pin "1") (pinfunction "1_1") (pintype "passive"))
      (node (ref "J1") (pin "1") (pinfunction "1_1") (pintype "passive"))
      (node (ref "J1") (pin "2") (pinfunction "2_2") (pintype "passive"))
      (node (ref "J4") (pin "4") (pinfunction "VDD_4") (pintype "passive"))
      (node (ref "Q1") (pin "2") (pinfunction "E_2") (pintype "passive"))
      (node (ref "R1") (pin "2") (pinfunction "2_2") (pintype "passive"))
      (node (ref "R10") (pin "2") (pinfunction "2_2") (pintype "passive"))
      (node (ref "R11") (pin "2") (pinfunction "2_2") (pintype "passive"))
      (node (ref "R15") (pin "2") (pinfunction "2_2") (pintype "passive"))
      (node (ref "R2") (pin "2") (pinfunction "2_2") (pintype "passive"))
      (node (ref "R20") (pin "2") (pinfunction "2_2") (pintype "passive"))
      (node (ref "R24") (pin "2") (pinfunction "2_2") (pintype "passive"))
      (node (ref "R25") (pin "2") (pinfunction "2_2") (pintype "passive"))
      (node (ref "R26") (pin "2") (pinfunction "2_2") (pintype "passive"))
      (node (ref "R27") (pin "2") (pinfunction "2_2") (pintype "passive"))
      (node (ref "R3") (pin "2") (pinfunction "2_2") (pintype "passive"))
      (node (ref "R5") (pin "2") (pinfunction "2_2") (pintype "passive"))
      (node (ref "R57") (pin "1") (pinfunction "1_1") (pintype "passive"))
      (node (ref "R7") (pin "2") (pinfunction "2_2") (pintype "passive"))
      (node (ref "R8") (pin "2") (pinfunction "2_2") (pintype "passive"))
      (node (ref "R9") (pin "2") (pinfunction "2_2") (pintype "passive"))
      (node (ref "U1") (pin "2") (pinfunction "VDD_2") (pintype "passive"))
      (node (ref "U2") (pin "6") (pinfunction "VDD_6") (pintype "passive"))
      (node (ref "U4") (pin "19") (pinfunction "VBAT_19") (pintype "passive"))
      (node (ref "U4") (pin "28") (pinfunction "VDD_28") (pintype "passive"))
      (node (ref "U4") (pin "42") (pinfunction "VDD_REG_42") (pintype "passive"))
      (node (ref "U4") (pin "54") (pinfunction "VDD_54") (pintype "passive"))
      (node (ref "U4") (pin "71") (pinfunction "VDD_71") (pintype "passive"))
      (node (ref "U4") (pin "84") (pinfunction "VDD_REG_84") (pintype "passive"))
      (node (ref "U4") (pin "96") (pinfunction "VDD_96") (pintype "passive"))
      (node (ref "U6") (pin "8") (pinfunction "VCC_8") (pintype "passive"))
    )
    (net (code "51") (name "3.3VA") (class "Default")
      (node (ref "FB2") (pin "2") (pinfunction "2_2") (pintype "passive"))
      (node (ref "R14") (pin "1") (pinfunction "1_1") (pintype "passive"))
      (node (ref "U4") (pin "10") (pinfunction "VDDA_10") (pintype "passive"))
    )
    (net (code "52") (name "GND") (class "Default")
      (node (ref "C1") (pin "2") (pinfunction "2_2") (pintype "passive"))
      (node (ref "C14") (pin "2") (pinfunction "2_2") (pintype "passive"))
      (node (ref "C15") (pin "2") (pinfunction "2_2") (pintype "passive"))
      (node (ref "C16") (pin "2") (pinfunction "2_2") (pintype "passive"))
      (node (ref "C17") (pin "2") (pinfunction "2_2") (pintype "passive"))
      (node (ref "C18") (pin "2") (pinfunction "2_2") (pintype "passive"))
      (node (ref "C19") (pin "2") (pinfunction "2_2") (pintype "passive"))
      (node (ref "C2") (pin "2") (pinfunction "2_2") (pintype "passive"))
      (node (ref "C20") (pin "2") (pinfunction "2_2") (pintype "passive"))
      (node (ref "C21") (pin "2") (pinfunction "2_2") (pintype "passive"))
      (node (ref "C22") (pin "2") (pinfunction "2_2") (pintype "passive"))
      (node (ref "C23") (pin "2") (pinfunction "2_2") (pintype "passive"))
      (node (ref "C24") (pin "2") (pinfunction "2_2") (pintype "passive"))
      (node (ref "C3") (pin "2") (pinfunction "2_2") (pintype "passive"))
      (node (ref "C4") (pin "2") (pinfunction "2_2") (pintype "passive"))
      (node (ref "C5") (pin "2") (pinfunction "2_2") (pintype "passive"))
      (node (ref "C6") (pin "2") (pinfunction "2_2") (pintype "passive"))
      (node (ref "C7") (pin "2") (pinfunction "2_2") (pintype "passive"))
      (node (ref "D11") (pin "1") (pinfunction "A_1") (pintype "passive"))
      (node (ref "D12") (pin "1") (pinfunction "A_1") (pintype "passive"))
      (node (ref "D7") (pin "1") (pinfunction "A_1") (pintype "passive"))
      (node (ref "D8") (pin "1") (pinfunction "A_1") (pintype "passive"))
      (node (ref "D9") (pin "1") (pinfunction "A_1") (pintype "passive"))
      (node (ref "FB1") (pin "1") (pinfunction "1_1") (pintype "passive"))
      (node (ref "FB3") (pin "1") (pinfunction "1_1") (pintype "passive"))
      (node (ref "FB4") (pin "1") (pinfunction "1_1") (pintype "passive"))
      (node (ref "J1") (pin "10") (pinfunction "10_10") (pintype "passive"))
      (node (ref "J1") (pin "12") (pinfunction "12_12") (pintype "passive"))
      (node (ref "J1") (pin "14") (pinfunction "14_14") (pintype "passive"))
      (node (ref "J1") (pin "16") (pinfunction "16_16") (pintype "passive"))
      (node (ref "J1") (pin "18") (pinfunction "18_18") (pintype "passive"))
      (node (ref "J1") (pin "20") (pinfunction "20_20") (pintype "passive"))
      (node (ref "J1") (pin "4") (pinfunction "4_4") (pintype "passive"))
      (node (ref "J1") (pin "6") (pinfunction "6_6") (pintype "passive"))
      (node (ref "J1") (pin "8") (pinfunction "8_8") (pintype "passive"))
      (node (ref "J2") (pin "5") (pinfunction "GND_5") (pintype "passive"))
      (node (ref "J3") (pin "5") (pinfunction "GND_5") (pintype "passive"))
      (node (ref "J4") (pin "10") (pinfunction "CGND_10") (pintype "passive"))
      (node (ref "J4") (pin "11") (pinfunction "CGND_11") (pintype "passive"))
      (node (ref "J4") (pin "12") (pinfunction "CGND_12") (pintype "passive"))
      (node (ref "J4") (pin "6") (pinfunction "GND_6") (pintype "passive"))
      (node (ref "J4") (pin "9") (pinfunction "CGND_9") (pintype "passive"))
      (node (ref "R13") (pin "1") (pinfunction "1_1") (pintype "passive"))
      (node (ref "R4") (pin "1") (pinfunction "1_1") (pintype "passive"))
      (node (ref "R6") (pin "1") (pinfunction "1_1") (pintype "passive"))
      (node (ref "SW1") (pin "1") (pintype "passive"))
      (node (ref "SW1") (pin "4") (pintype "passive"))
      (node (ref "SW2") (pin "1") (pintype "passive"))
      (node (ref "SW2") (pin "4") (pintype "passive"))
      (node (ref "U1") (pin "1") (pinfunction "VSS_1") (pintype "passive"))
      (node (ref "U1") (pin "14") (pinfunction "VSS_14") (pintype "passive"))
      (node (ref "U1") (pin "24") (pinfunction "C_24") (pintype "passive"))
      (node (ref "U2") (pin "29") (pinfunction "GND_29") (pintype "passive"))
      (node (ref "U2") (pin "3") (pinfunction "GND_3") (pintype "passive"))
      (node (ref "U4") (pin "31") (pinfunction "VSS_31") (pintype "passive"))
      (node (ref "U4") (pin "41") (pinfunction "VSS_41") (pintype "passive"))
      (node (ref "U4") (pin "55") (pinfunction "VSS_55") (pintype "passive"))
      (node (ref "U4") (pin "72") (pinfunction "VSS_72") (pintype "passive"))
      (node (ref "U4") (pin "83") (pinfunction "VSS_83") (pintype "passive"))
      (node (ref "U4") (pin "97") (pinfunction "VSS_97") (pintype "passive"))
      (node (ref "U6") (pin "1") (pinfunction "A0_1") (pintype "passive"))
      (node (ref "U6") (pin "2") (pinfunction "A1_2") (pintype "passive"))
      (node (ref "U6") (pin "3") (pinfunction "A2_3") (pintype "passive"))
      (node (ref "U6") (pin "4") (pinfunction "GND_4") (pintype "passive"))
      (node (ref "U6") (pin "7") (pinfunction "WP_7") (pintype "passive"))
    )
    (net (code "53") (name "GNDA") (class "Default")
      (node (ref "C12") (pin "2") (pinfunction "2_2") (pintype "passive"))
      (node (ref "C8") (pin "1") (pinfunction "1_1") (pintype "passive"))
      (node (ref "FB3") (pin "2") (pinfunction "2_2") (pintype "passive"))
      (node (ref "R23") (pin "1") (pinfunction "1_1") (pintype "passive"))
      (node (ref "R28") (pin "1") (pinfunction "1_1") (pintype "passive"))
      (node (ref "SPK1") (pin "2") (pinfunction "-_2") (pintype "passive"))
      (node (ref "U3") (pin "2") (pinfunction "A_2") (pintype "passive"))
      (node (ref "U4") (pin "11") (pinfunction "VSSA_11") (pintype "passive"))
      (node (ref "U4") (pin "15") (pinfunction "VREFN_15") (pintype "passive"))
      (node (ref "U5") (pin "2") (pinfunction "V-_2") (pintype "passive"))
      (node (ref "U5") (pin "4") (pinfunction "GND_4") (pintype "passive"))
    )
    (net (code "54") (name "Net-(C9-Pad2)") (class "Default")
      (node (ref "C9") (pin "2") (pinfunction "2_2") (pintype "passive"))
      (node (ref "R23") (pin "2") (pinfunction "2_2") (pintype "passive"))
    )
    (net (code "55") (name "Net-(C10-Pad2)") (class "Default")
      (node (ref "C10") (pin "2") (pinfunction "2_2") (pintype "passive"))
      (node (ref "C11") (pin "1") (pinfunction "1_1") (pintype "passive"))
      (node (ref "U5") (pin "5") (pintype "passive"))
    )
    (net (code "56") (name "Net-(C11-Pad2)") (class "Default")
      (node (ref "C11") (pin "2") (pinfunction "2_2") (pintype "passive"))
      (node (ref "C13") (pin "1") (pinfunction "1_1") (pintype "passive"))
    )
    (net (code "57") (name "Net-(C13-Pad2)") (class "Default")
      (node (ref "C13") (pin "2") (pinfunction "2_2") (pintype "passive"))
      (node (ref "R28") (pin "2") (pinfunction "2_2") (pintype "passive"))
    )
    (net (code "58") (name "Net-(D1-A)") (class "Default")
      (node (ref "D1") (pin "1") (pinfunction "A_1") (pintype "passive"))
      (node (ref "J3") (pin "1") (pinfunction "VBUS_1") (pintype "passive"))
      (node (ref "R17") (pin "2") (pinfunction "2_2") (pintype "passive"))
    )
    (net (code "59") (name "Net-(D2-A)") (class "Default")
      (node (ref "D2") (pin "1") (pinfunction "A_1") (pintype "passive"))
      (node (ref "R7") (pin "1") (pinfunction "1_1") (pintype "passive"))
    )
    (net (code "60") (name "Net-(D3-A)") (class "Default")
      (node (ref "D3") (pin "1") (pinfunction "A_1") (pintype "passive"))
      (node (ref "R8") (pin "1") (pinfunction "1_1") (pintype "passive"))
    )
    (net (code "61") (name "Net-(D4-A)") (class "Default")
      (node (ref "D4") (pin "1") (pinfunction "A_1") (pintype "passive"))
      (node (ref "R9") (pin "1") (pinfunction "1_1") (pintype "passive"))
    )
    (net (code "62") (name "Net-(D5-A)") (class "Default")
      (node (ref "D5") (pin "1") (pinfunction "A_1") (pintype "passive"))
      (node (ref "R10") (pin "1") (pinfunction "1_1") (pintype "passive"))
    )
    (net (code "63") (name "Net-(D6-A)") (class "Default")
      (node (ref "D6") (pin "1") (pinfunction "A_1") (pintype "passive"))
      (node (ref "R11") (pin "1") (pinfunction "1_1") (pintype "passive"))
    )
    (net (code "64") (name "Net-(D11-K)") (class "Default")
      (node (ref "D11") (pin "2") (pinfunction "K_2") (pintype "passive"))
      (node (ref "J3") (pin "2") (pinfunction "D-_2") (pintype "passive"))
      (node (ref "R18") (pin "2") (pinfunction "2_2") (pintype "passive"))
    )
    (net (code "65") (name "Net-(D12-K)") (class "Default")
      (node (ref "D12") (pin "2") (pinfunction "K_2") (pintype "passive"))
      (node (ref "J3") (pin "3") (pinfunction "D+_3") (pintype "passive"))
      (node (ref "R16") (pin "1") (pinfunction "1_1") (pintype "passive"))
      (node (ref "R19") (pin "2") (pinfunction "2_2") (pintype "passive"))
    )
    (net (code "66") (name "Net-(D13-K)") (class "Default")
      (node (ref "C9") (pin "1") (pinfunction "1_1") (pintype "passive"))
      (node (ref "D13") (pin "2") (pinfunction "K_2") (pintype "passive"))
      (node (ref "D14") (pin "2") (pinfunction "K_2") (pintype "passive"))
    )
    (net (code "67") (name "Net-(FB1-Pad2)") (class "Default")
      (node (ref "FB1") (pin "2") (pinfunction "2_2") (pintype "passive"))
      (node (ref "J2") (pin "6") (pinfunction "CGND_6") (pintype "passive"))
      (node (ref "J2") (pin "7") (pinfunction "CGND_7") (pintype "passive"))
      (node (ref "J2") (pin "8") (pinfunction "CGND_8") (pintype "passive"))
      (node (ref "J2") (pin "9") (pinfunction "CGND_9") (pintype "passive"))
    )
    (net (code "68") (name "Net-(FB4-Pad2)") (class "Default")
      (node (ref "FB4") (pin "2") (pinfunction "2_2") (pintype "passive"))
      (node (ref "J3") (pin "6") (pinfunction "CGND_6") (pintype "passive"))
      (node (ref "J3") (pin "7") (pinfunction "CGND_7") (pintype "passive"))
      (node (ref "J3") (pin "8") (pinfunction "CGND_8") (pintype "passive"))
      (node (ref "J3") (pin "9") (pinfunction "CGND_9") (pintype "passive"))
    )
    (net (code "69") (name "Net-(Q1-C)") (class "Default")
      (node (ref "Q1") (pin "3") (pinfunction "C_3") (pintype "passive"))
      (node (ref "R16") (pin "2") (pinfunction "2_2") (pintype "passive"))
    )
    (net (code "70") (name "Net-(SPK1-+)") (class "Default")
      (node (ref "C10") (pin "1") (pinfunction "1_1") (pintype "passive"))
      (node (ref "SPK1") (pin "1") (pinfunction "+_1") (pintype "passive"))
    )
    (net (code "71") (name "Net-(U1-VCI)") (class "Default")
      (node (ref "R57") (pin "2") (pinfunction "2_2") (pintype "passive"))
      (node (ref "U1") (pin "3") (pinfunction "VCI_3") (pintype "passive"))
    )
    (net (code "72") (name "Net-(U4-RTCX1)") (class "Default")
      (node (ref "C4") (pin "1") (pinfunction "1_1") (pintype "passive"))
      (node (ref "R21") (pin "1") (pinfunction "1_1") (pintype "passive"))
      (node (ref "U4") (pin "16") (pinfunction "RTCX1_16") (pintype "passive"))
      (node (ref "X1") (pin "1") (pinfunction "1_1") (pintype "passive"))
    )
    (net (code "73") (name "Net-(U4-RTCX2)") (class "Default")
      (node (ref "C5") (pin "1") (pinfunction "1_1") (pintype "passive"))
      (node (ref "R21") (pin "2") (pinfunction "2_2") (pintype "passive"))
      (node (ref "U4") (pin "18") (pinfunction "RTCX2_18") (pintype "passive"))
      (node (ref "X1") (pin "2") (pinfunction "2_2") (pintype "passive"))
    )
    (net (code "74") (name "Net-(U4-XTAL1)") (class "Default")
      (node (ref "C6") (pin "1") (pinfunction "1_1") (pintype "passive"))
      (node (ref "R22") (pin "1") (pinfunction "1_1") (pintype "passive"))
      (node (ref "U4") (pin "22") (pinfunction "XTAL1_22") (pintype "passive"))
      (node (ref "X2") (pin "1") (pinfunction "1_1") (pintype "passive"))
    )
    (net (code "75") (name "Net-(U4-XTAL2)") (class "Default")
      (node (ref "C7") (pin "1") (pinfunction "1_1") (pintype "passive"))
      (node (ref "R22") (pin "2") (pinfunction "2_2") (pintype "passive"))
      (node (ref "U4") (pin "23") (pinfunction "XTAL2_23") (pintype "passive"))
      (node (ref "X2") (pin "2") (pinfunction "2_2") (pintype "passive"))
    )
    (net (code "76") (name "Net-(U5-BYP)") (class "Default")
      (node (ref "C12") (pin "1") (pinfunction "1_1") (pintype "passive"))
      (node (ref "U5") (pin "7") (pinfunction "BYP_7") (pintype "passive"))
    )
    (net (code "77") (name "Net-(U5-V+)") (class "Default")
      (node (ref "R23") (pin "3") (pintype "passive"))
      (node (ref "U5") (pin "3") (pinfunction "V+_3") (pintype "passive"))
    )
    (net (code "78") (name "VBL") (class "Default")
      (node (ref "U1") (pin "23") (pinfunction "A_23") (pintype "passive"))
    )
    (net (code "79") (name "VCC") (class "Default")
      (node (ref "C8") (pin "2") (pinfunction "2_2") (pintype "passive"))
      (node (ref "U5") (pin "6") (pinfunction "VS_6") (pintype "passive"))
    )
    (net (code "80") (name "VUSB") (class "Default")
      (node (ref "D1") (pin "2") (pinfunction "K_2") (pintype "passive"))
      (node (ref "J2") (pin "1") (pinfunction "VBUS_1") (pintype "passive"))
      (node (ref "R12") (pin "2") (pinfunction "2_2") (pintype "passive"))
      (node (ref "U2") (pin "7") (pinfunction "REGIN_7") (pintype "passive"))
      (node (ref "U2") (pin "8") (pinfunction "VBUS_8") (pintype "passive"))
    )
    (net (code "81") (name "unconnected-(J1-Pad15)") (class "Default")
      (node (ref "J1") (pin "15") (pinfunction "15_15") (pintype "passive"))
    )
    (net (code "82") (name "unconnected-(J1-Pad17)") (class "Default")
      (node (ref "J1") (pin "17") (pinfunction "17_17") (pintype "passive"))
    )
    (net (code "83") (name "unconnected-(J1-Pad19)") (class "Default")
      (node (ref "J1") (pin "19") (pinfunction "19_19") (pintype "passive"))
    )
    (net (code "84") (name "unconnected-(J2-ID-Pad4)") (class "Default")
      (node (ref "J2") (pin "4") (pinfunction "ID_4") (pintype "passive"))
    )
    (net (code "85") (name "unconnected-(J3-ID-Pad4)") (class "Default")
      (node (ref "J3") (pin "4") (pinfunction "ID_4") (pintype "passive"))
    )
    (net (code "86") (name "unconnected-(J4-NC{slash}DAT1-Pad8)") (class "Default")
      (node (ref "J4") (pin "8") (pinfunction "NC/DAT1_8") (pintype "passive"))
    )
    (net (code "87") (name "unconnected-(J4-NC{slash}DAT2-Pad1)") (class "Default")
      (node (ref "J4") (pin "1") (pinfunction "NC/DAT2_1") (pintype "passive"))
    )
    (net (code "88") (name "unconnected-(U1-NC-Pad8)") (class "Default")
      (node (ref "U1") (pin "8") (pinfunction "NC_8") (pintype "passive"))
    )
    (net (code "89") (name "unconnected-(U1-NC-Pad9)") (class "Default")
      (node (ref "U1") (pin "9") (pinfunction "NC_9") (pintype "passive"))
    )
    (net (code "90") (name "unconnected-(U1-NC-Pad10)") (class "Default")
      (node (ref "U1") (pin "10") (pinfunction "NC_10") (pintype "passive"))
    )
    (net (code "91") (name "unconnected-(U1-NC-Pad11)") (class "Default")
      (node (ref "U1") (pin "11") (pinfunction "NC_11") (pintype "passive"))
    )
    (net (code "92") (name "unconnected-(U1-NC-Pad12)") (class "Default")
      (node (ref "U1") (pin "12") (pinfunction "NC_12") (pintype "passive"))
    )
    (net (code "93") (name "unconnected-(U1-NC-Pad13)") (class "Default")
      (node (ref "U1") (pin "13") (pinfunction "NC_13") (pintype "passive"))
    )
    (net (code "94") (name "unconnected-(U1-NC-Pad16)") (class "Default")
      (node (ref "U1") (pin "16") (pinfunction "NC_16") (pintype "passive"))
    )
    (net (code "95") (name "unconnected-(U1-NC-Pad17)") (class "Default")
      (node (ref "U1") (pin "17") (pinfunction "NC_17") (pintype "passive"))
    )
    (net (code "96") (name "unconnected-(U1-NC-Pad18)") (class "Default")
      (node (ref "U1") (pin "18") (pinfunction "NC_18") (pintype "passive"))
    )
    (net (code "97") (name "unconnected-(U1-NC-Pad19)") (class "Default")
      (node (ref "U1") (pin "19") (pinfunction "NC_19") (pintype "passive"))
    )
    (net (code "98") (name "unconnected-(U1-NC-Pad20)") (class "Default")
      (node (ref "U1") (pin "20") (pinfunction "NC_20") (pintype "passive"))
    )
    (net (code "99") (name "unconnected-(U1-NC-Pad21)") (class "Default")
      (node (ref "U1") (pin "21") (pinfunction "NC_21") (pintype "passive"))
    )
    (net (code "100") (name "unconnected-(U1-NC-Pad22)") (class "Default")
      (node (ref "U1") (pin "22") (pinfunction "NC_22") (pintype "passive"))
    )
    (net (code "101") (name "unconnected-(U2-CTS-Pad23)") (class "Default")
      (node (ref "U2") (pin "23") (pinfunction "CTS_23") (pintype "passive"))
    )
    (net (code "102") (name "unconnected-(U2-DCD-Pad1)") (class "Default")
      (node (ref "U2") (pin "1") (pinfunction "DCD_1") (pintype "passive"))
    )
    (net (code "103") (name "unconnected-(U2-DSR-Pad27)") (class "Default")
      (node (ref "U2") (pin "27") (pinfunction "DSR_27") (pintype "passive"))
    )
    (net (code "104") (name "unconnected-(U2-DTR-Pad28)") (class "Default")
      (node (ref "U2") (pin "28") (pinfunction "DTR_28") (pintype "passive"))
    )
    (net (code "105") (name "unconnected-(U2-NC-Pad10)") (class "Default")
      (node (ref "U2") (pin "10") (pinfunction "NC_10") (pintype "passive"))
    )
    (net (code "106") (name "unconnected-(U2-NC-Pad13)") (class "Default")
      (node (ref "U2") (pin "13") (pinfunction "NC_13") (pintype "passive"))
    )
    (net (code "107") (name "unconnected-(U2-NC-Pad14)") (class "Default")
      (node (ref "U2") (pin "14") (pinfunction "NC_14") (pintype "passive"))
    )
    (net (code "108") (name "unconnected-(U2-NC-Pad15)") (class "Default")
      (node (ref "U2") (pin "15") (pinfunction "NC_15") (pintype "passive"))
    )
    (net (code "109") (name "unconnected-(U2-NC-Pad16)") (class "Default")
      (node (ref "U2") (pin "16") (pinfunction "NC_16") (pintype "passive"))
    )
    (net (code "110") (name "unconnected-(U2-NC-Pad17)") (class "Default")
      (node (ref "U2") (pin "17") (pinfunction "NC_17") (pintype "passive"))
    )
    (net (code "111") (name "unconnected-(U2-NC-Pad18)") (class "Default")
      (node (ref "U2") (pin "18") (pinfunction "NC_18") (pintype "passive"))
    )
    (net (code "112") (name "unconnected-(U2-NC-Pad19)") (class "Default")
      (node (ref "U2") (pin "19") (pinfunction "NC_19") (pintype "passive"))
    )
    (net (code "113") (name "unconnected-(U2-NC-Pad20)") (class "Default")
      (node (ref "U2") (pin "20") (pinfunction "NC_20") (pintype "passive"))
    )
    (net (code "114") (name "unconnected-(U2-NC-Pad21)") (class "Default")
      (node (ref "U2") (pin "21") (pinfunction "NC_21") (pintype "passive"))
    )
    (net (code "115") (name "unconnected-(U2-NC-Pad22)") (class "Default")
      (node (ref "U2") (pin "22") (pinfunction "NC_22") (pintype "passive"))
    )
    (net (code "116") (name "unconnected-(U2-RI-Pad2)") (class "Default")
      (node (ref "U2") (pin "2") (pinfunction "RI_2") (pintype "passive"))
    )
    (net (code "117") (name "unconnected-(U2-RTS-Pad24)") (class "Default")
      (node (ref "U2") (pin "24") (pinfunction "RTS_24") (pintype "passive"))
    )
    (net (code "118") (name "unconnected-(U2-SUSPEND-Pad11)") (class "Default")
      (node (ref "U2") (pin "11") (pinfunction "SUSPEND_11") (pintype "passive"))
    )
    (net (code "119") (name "unconnected-(U4-NC-Pad13)") (class "Default")
      (node (ref "U4") (pin "13") (pinfunction "NC_13") (pintype "passive"))
    )
    (net (code "120") (name "unconnected-(U4-P0:4-Pad81)") (class "Default")
      (node (ref "U4") (pin "81") (pinfunction "P0:4_81") (pintype "passive"))
    )
    (net (code "121") (name "unconnected-(U4-P0:5-Pad80)") (class "Default")
      (node (ref "U4") (pin "80") (pinfunction "P0:5_80") (pintype "passive"))
    )
    (net (code "122") (name "unconnected-(U4-P0:10-Pad48)") (class "Default")
      (node (ref "U4") (pin "48") (pinfunction "P0:10_48") (pintype "passive"))
    )
    (net (code "123") (name "unconnected-(U4-P0:11-Pad49)") (class "Default")
      (node (ref "U4") (pin "49") (pinfunction "P0:11_49") (pintype "passive"))
    )
    (net (code "124") (name "unconnected-(U4-P0:19-Pad59)") (class "Default")
      (node (ref "U4") (pin "59") (pinfunction "P0:19_59") (pintype "passive"))
    )
    (net (code "125") (name "unconnected-(U4-P0:20-Pad58)") (class "Default")
      (node (ref "U4") (pin "58") (pinfunction "P0:20_58") (pintype "passive"))
    )
    (net (code "126") (name "unconnected-(U4-P0:21-Pad57)") (class "Default")
      (node (ref "U4") (pin "57") (pinfunction "P0:21_57") (pintype "passive"))
    )
    (net (code "127") (name "unconnected-(U4-P1:0-Pad95)") (class "Default")
      (node (ref "U4") (pin "95") (pinfunction "P1:0_95") (pintype "passive"))
    )
    (net (code "128") (name "unconnected-(U4-P1:14-Pad89)") (class "Default")
      (node (ref "U4") (pin "89") (pinfunction "P1:14_89") (pintype "passive"))
    )
    (net (code "129") (name "unconnected-(U4-P1:15-Pad88)") (class "Default")
      (node (ref "U4") (pin "88") (pinfunction "P1:15_88") (pintype "passive"))
    )
    (net (code "130") (name "unconnected-(U4-P1:16-Pad87)") (class "Default")
      (node (ref "U4") (pin "87") (pinfunction "P1:16_87") (pintype "passive"))
    )
    (net (code "131") (name "unconnected-(U4-P1:17-Pad86)") (class "Default")
      (node (ref "U4") (pin "86") (pinfunction "P1:17_86") (pintype "passive"))
    )
    (net (code "132") (name "unconnected-(U4-P1:23-Pad37)") (class "Default")
      (node (ref "U4") (pin "37") (pinfunction "P1:23_37") (pintype "passive"))
    )
    (net (code "133") (name "unconnected-(U4-P1:24-Pad38)") (class "Default")
      (node (ref "U4") (pin "38") (pinfunction "P1:24_38") (pintype "passive"))
    )
    (net (code "134") (name "unconnected-(U4-P1:25-Pad39)") (class "Default")
      (node (ref "U4") (pin "39") (pinfunction "P1:25_39") (pintype "passive"))
    )
    (net (code "135") (name "unconnected-(U4-P1:26-Pad40)") (class "Default")
      (node (ref "U4") (pin "40") (pinfunction "P1:26_40") (pintype "passive"))
    )
    (net (code "136") (name "unconnected-(U4-P1:27-Pad43)") (class "Default")
      (node (ref "U4") (pin "43") (pinfunction "P1:27_43") (pintype "passive"))
    )
    (net (code "137") (name "unconnected-(U4-P1:28-Pad44)") (class "Default")
      (node (ref "U4") (pin "44") (pinfunction "P1:28_44") (pintype "passive"))
    )
    (net (code "138") (name "unconnected-(U4-P1:29-Pad45)") (class "Default")
      (node (ref "U4") (pin "45") (pinfunction "P1:29_45") (pintype "passive"))
    )
    (net (code "139") (name "unconnected-(U4-P1:31-Pad20)") (class "Default")
      (node (ref "U4") (pin "20") (pinfunction "P1:31_20") (pintype "passive"))
    )
    (net (code "140") (name "unconnected-(U4-P2:0-Pad75)") (class "Default")
      (node (ref "U4") (pin "75") (pinfunction "P2:0_75") (pintype "passive"))
    )
    (net (code "141") (name "unconnected-(U4-P2:1-Pad74)") (class "Default")
      (node (ref "U4") (pin "74") (pinfunction "P2:1_74") (pintype "passive"))
    )
    (net (code "142") (name "unconnected-(U4-P2:2-Pad73)") (class "Default")
      (node (ref "U4") (pin "73") (pinfunction "P2:2_73") (pintype "passive"))
    )
    (net (code "143") (name "unconnected-(U4-P2:3-Pad70)") (class "Default")
      (node (ref "U4") (pin "70") (pinfunction "P2:3_70") (pintype "passive"))
    )
    (net (code "144") (name "unconnected-(U4-P2:5-Pad68)") (class "Default")
      (node (ref "U4") (pin "68") (pinfunction "P2:5_68") (pintype "passive"))
    )
    (net (code "145") (name "unconnected-(U4-P2:6-Pad67)") (class "Default")
      (node (ref "U4") (pin "67") (pinfunction "P2:6_67") (pintype "passive"))
    )
    (net (code "146") (name "unconnected-(U4-P2:7-Pad66)") (class "Default")
      (node (ref "U4") (pin "66") (pinfunction "P2:7_66") (pintype "passive"))
    )
    (net (code "147") (name "unconnected-(U4-P2:8-Pad65)") (class "Default")
      (node (ref "U4") (pin "65") (pinfunction "P2:8_65") (pintype "passive"))
    )
    (net (code "148") (name "unconnected-(U4-P2:13-Pad50)") (class "Default")
      (node (ref "U4") (pin "50") (pinfunction "P2:13_50") (pintype "passive"))
    )
    (net (code "149") (name "unconnected-(U4-P2:69-Pad69)") (class "Default")
      (node (ref "U4") (pin "69") (pinfunction "P2:69_69") (pintype "passive"))
    )
    (net (code "150") (name "unconnected-(U4-P4:28-Pad82)") (class "Default")
      (node (ref "U4") (pin "82") (pinfunction "P4:28_82") (pintype "passive"))
    )
    (net (code "151") (name "unconnected-(U4-P4:29-Pad85)") (class "Default")
      (node (ref "U4") (pin "85") (pinfunction "P4:29_85") (pintype "passive"))
    )
    (net (code "152") (name "unconnected-(U5-AG-Pad1)") (class "Default")
      (node (ref "U5") (pin "1") (pinfunction "AG_1") (pintype "passive"))
    )
    (net (code "153") (name "unconnected-(U5-AG-Pad8)") (class "Default")
      (node (ref "U5") (pin "8") (pinfunction "AG_8") (pintype "passive"))
    )
  )
)
